# RF-UNIT.net
KiCad netlist of a schematic drawn in Altium Designer
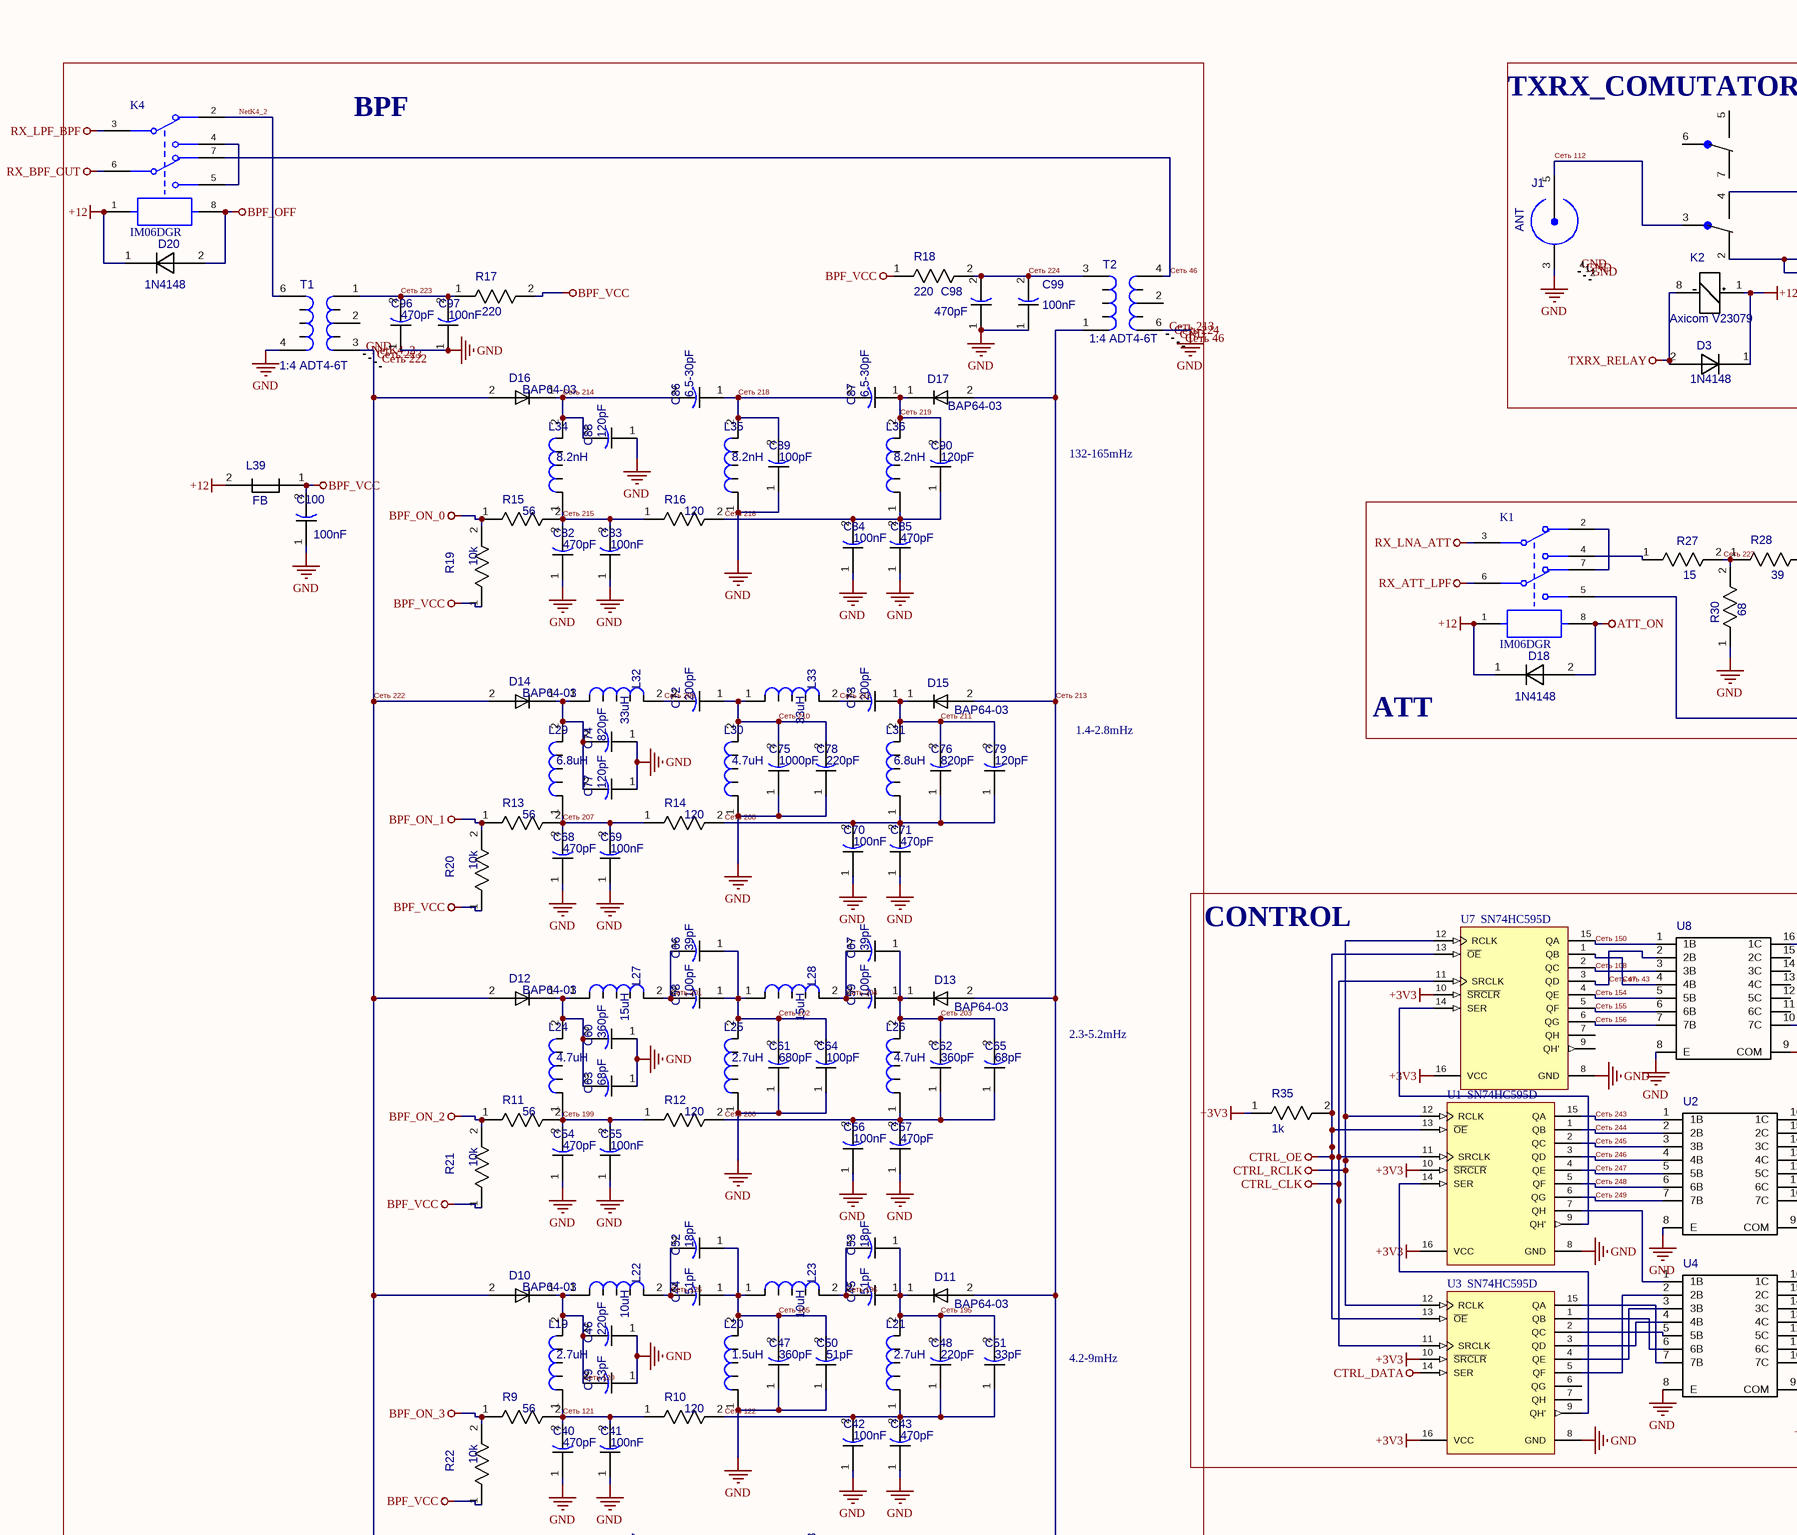
[diagram p0: RF-UNIT.SCHDOC, top left]
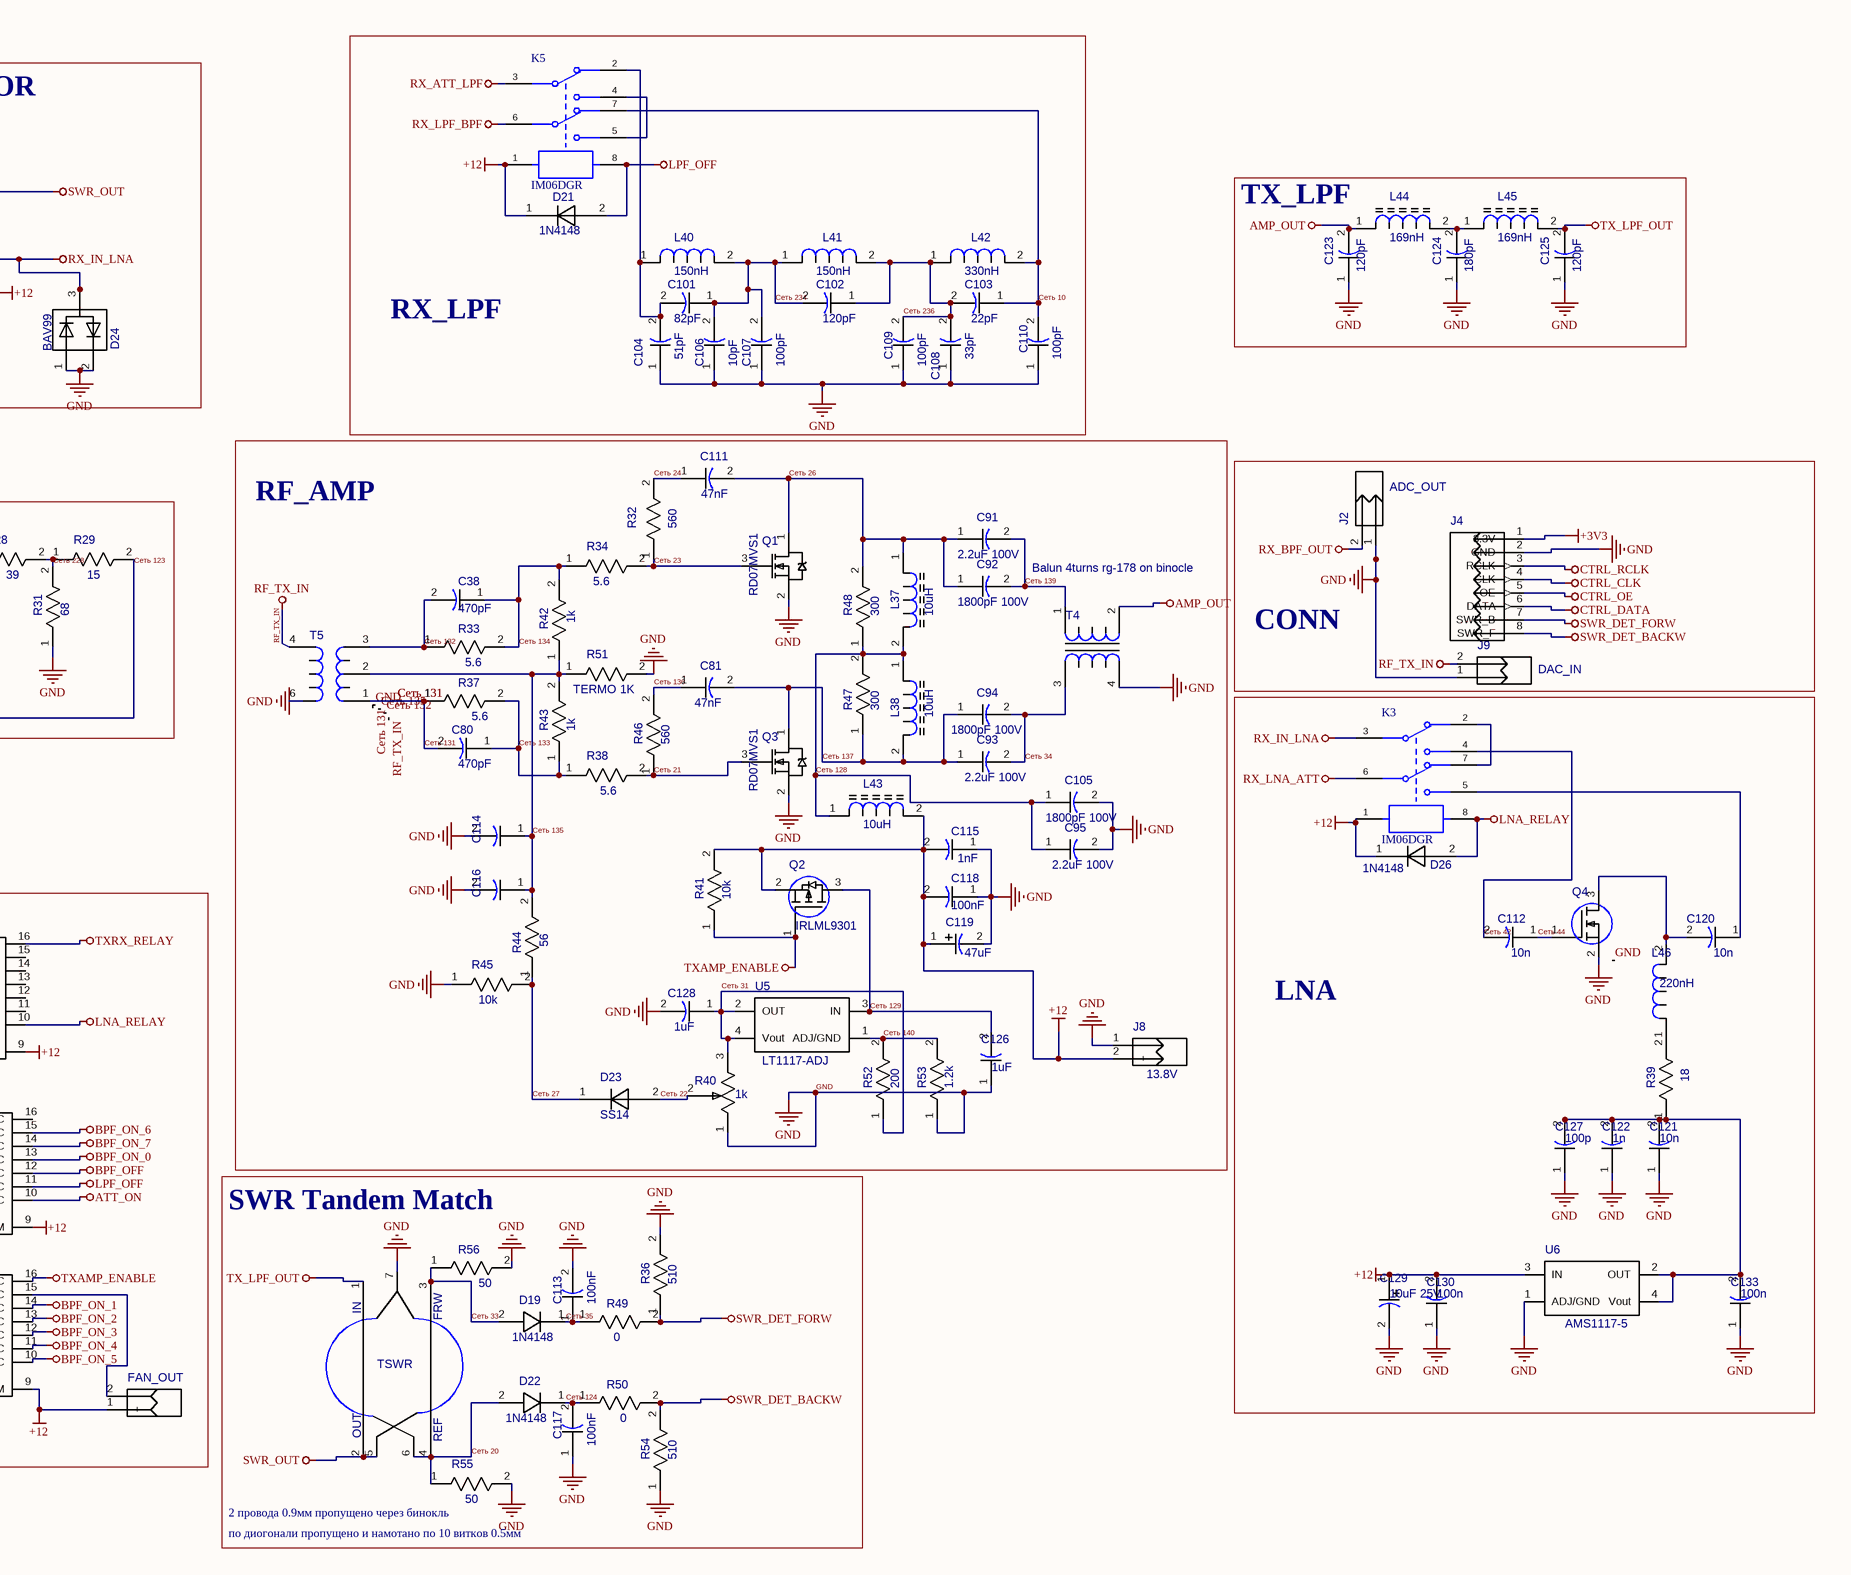
[diagram p1: RF-UNIT.SCHDOC, top right]
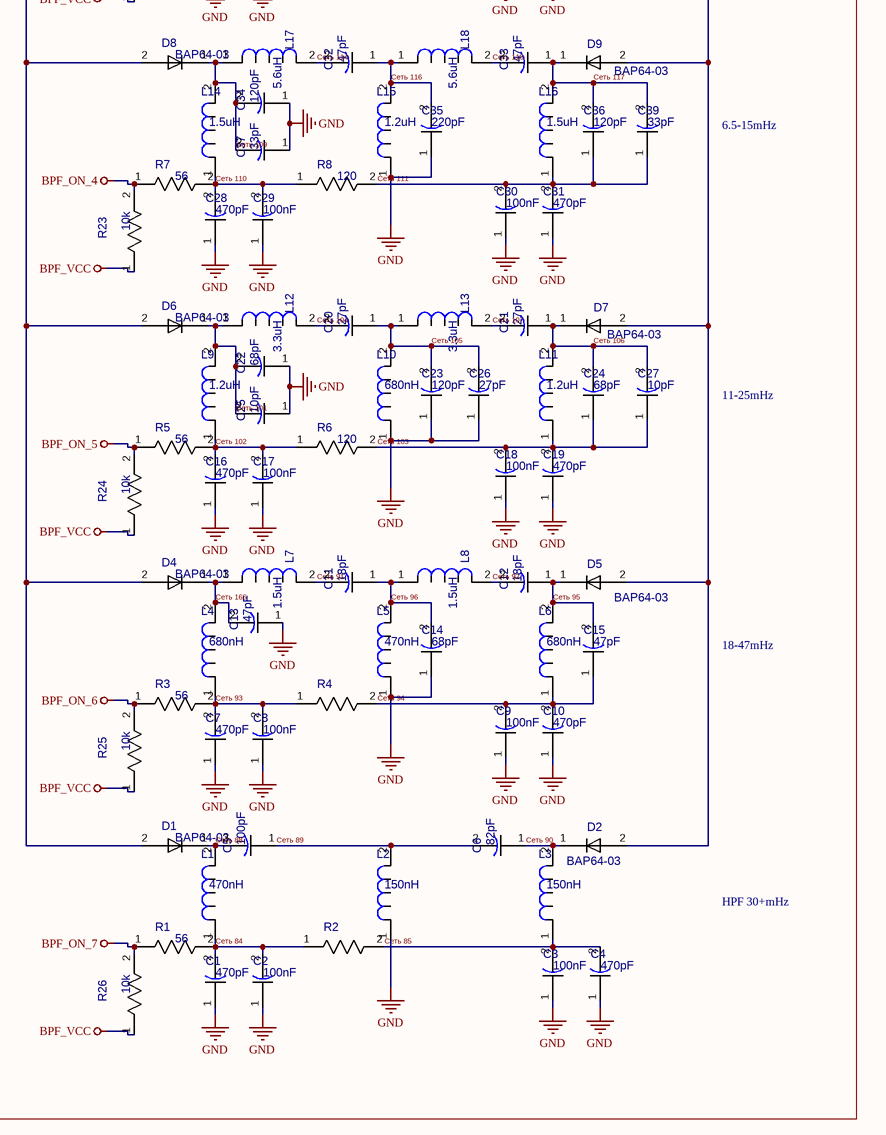
[diagram p2: RF-UNIT.SCHDOC, bottom left]

(export (version "E")
  (design (tool "Eeschema 10.0.6"))
  (components
    (comp (ref "C1")
      (value "470pF")
      (footprint "CAP_0805")
      (description "CAP_0805")
      (libsource (lib "*") (part "CAP_0805"))
    )
    (comp (ref "C2")
      (value "100nF")
      (footprint "CAP_0805")
      (description "CAP_0805")
      (libsource (lib "*") (part "CAP_0805"))
    )
    (comp (ref "C3")
      (value "100nF")
      (footprint "CAP_0805")
      (description "CAP_0805")
      (libsource (lib "*") (part "CAP_0805"))
    )
    (comp (ref "C4")
      (value "470pF")
      (footprint "CAP_0805")
      (description "CAP_0805")
      (libsource (lib "*") (part "CAP_0805"))
    )
    (comp (ref "C5")
      (value "100pF")
      (footprint "CAP_0805")
      (description "CAP_0805")
      (libsource (lib "*") (part "CAP_0805"))
    )
    (comp (ref "C6")
      (value "82pF")
      (footprint "CAP_0805")
      (description "CAP_0805")
      (libsource (lib "*") (part "CAP_0805"))
    )
    (comp (ref "C7")
      (value "470pF")
      (footprint "CAP_0805")
      (description "CAP_0805")
      (libsource (lib "*") (part "CAP_0805"))
    )
    (comp (ref "C8")
      (value "100nF")
      (footprint "CAP_0805")
      (description "CAP_0805")
      (libsource (lib "*") (part "CAP_0805"))
    )
    (comp (ref "C9")
      (value "100nF")
      (footprint "CAP_0805")
      (description "CAP_0805")
      (libsource (lib "*") (part "CAP_0805"))
    )
    (comp (ref "C10")
      (value "470pF")
      (footprint "CAP_0805")
      (description "CAP_0805")
      (libsource (lib "*") (part "CAP_0805"))
    )
    (comp (ref "C11")
      (value "18pF")
      (footprint "CAP_0805")
      (description "CAP_0805")
      (libsource (lib "*") (part "CAP_0805"))
    )
    (comp (ref "C12")
      (value "18pF")
      (footprint "CAP_0805")
      (description "CAP_0805")
      (libsource (lib "*") (part "CAP_0805"))
    )
    (comp (ref "C13")
      (value "47pF")
      (footprint "CAP_0805")
      (description "CAP_0805")
      (libsource (lib "*") (part "CAP_0805"))
    )
    (comp (ref "C14")
      (value "68pF")
      (footprint "CAP_0805")
      (description "CAP_0805")
      (libsource (lib "*") (part "CAP_0805"))
    )
    (comp (ref "C15")
      (value "47pF")
      (footprint "CAP_0805")
      (description "CAP_0805")
      (libsource (lib "*") (part "CAP_0805"))
    )
    (comp (ref "C16")
      (value "470pF")
      (footprint "CAP_0805")
      (description "CAP_0805")
      (libsource (lib "*") (part "CAP_0805"))
    )
    (comp (ref "C17")
      (value "100nF")
      (footprint "CAP_0805")
      (description "CAP_0805")
      (libsource (lib "*") (part "CAP_0805"))
    )
    (comp (ref "C18")
      (value "100nF")
      (footprint "CAP_0805")
      (description "CAP_0805")
      (libsource (lib "*") (part "CAP_0805"))
    )
    (comp (ref "C19")
      (value "470pF")
      (footprint "CAP_0805")
      (description "CAP_0805")
      (libsource (lib "*") (part "CAP_0805"))
    )
    (comp (ref "C20")
      (value "27pF")
      (footprint "CAP_0805")
      (description "CAP_0805")
      (libsource (lib "*") (part "CAP_0805"))
    )
    (comp (ref "C21")
      (value "27pF")
      (footprint "CAP_0805")
      (description "CAP_0805")
      (libsource (lib "*") (part "CAP_0805"))
    )
    (comp (ref "C22")
      (value "68pF")
      (footprint "CAP_0805")
      (description "CAP_0805")
      (libsource (lib "*") (part "CAP_0805"))
    )
    (comp (ref "C23")
      (value "120pF")
      (footprint "CAP_0805")
      (description "CAP_0805")
      (libsource (lib "*") (part "CAP_0805"))
    )
    (comp (ref "C24")
      (value "68pF")
      (footprint "CAP_0805")
      (description "CAP_0805")
      (libsource (lib "*") (part "CAP_0805"))
    )
    (comp (ref "C25")
      (value "10pF")
      (footprint "CAP_0805")
      (description "CAP_0805")
      (libsource (lib "*") (part "CAP_0805"))
    )
    (comp (ref "C26")
      (value "27pF")
      (footprint "CAP_0805")
      (description "CAP_0805")
      (libsource (lib "*") (part "CAP_0805"))
    )
    (comp (ref "C27")
      (value "10pF")
      (footprint "CAP_0805")
      (description "CAP_0805")
      (libsource (lib "*") (part "CAP_0805"))
    )
    (comp (ref "C28")
      (value "470pF")
      (footprint "CAP_0805")
      (description "CAP_0805")
      (libsource (lib "*") (part "CAP_0805"))
    )
    (comp (ref "C29")
      (value "100nF")
      (footprint "CAP_0805")
      (description "CAP_0805")
      (libsource (lib "*") (part "CAP_0805"))
    )
    (comp (ref "C30")
      (value "100nF")
      (footprint "CAP_0805")
      (description "CAP_0805")
      (libsource (lib "*") (part "CAP_0805"))
    )
    (comp (ref "C31")
      (value "470pF")
      (footprint "CAP_0805")
      (description "CAP_0805")
      (libsource (lib "*") (part "CAP_0805"))
    )
    (comp (ref "C32")
      (value "47pF")
      (footprint "CAP_0805")
      (description "CAP_0805")
      (libsource (lib "*") (part "CAP_0805"))
    )
    (comp (ref "C33")
      (value "47pF")
      (footprint "CAP_0805")
      (description "CAP_0805")
      (libsource (lib "*") (part "CAP_0805"))
    )
    (comp (ref "C34")
      (value "120pF")
      (footprint "CAP_0805")
      (description "CAP_0805")
      (libsource (lib "*") (part "CAP_0805"))
    )
    (comp (ref "C35")
      (value "220pF")
      (footprint "CAP_0805")
      (description "CAP_0805")
      (libsource (lib "*") (part "CAP_0805"))
    )
    (comp (ref "C36")
      (value "120pF")
      (footprint "CAP_0805")
      (description "CAP_0805")
      (libsource (lib "*") (part "CAP_0805"))
    )
    (comp (ref "C37")
      (value "33pF")
      (footprint "CAP_0805")
      (description "CAP_0805")
      (libsource (lib "*") (part "CAP_0805"))
    )
    (comp (ref "C38")
      (value "470pF")
      (footprint "CAP_0805")
      (description "CAP_0805")
      (libsource (lib "*") (part "CAP_0805"))
    )
    (comp (ref "C39")
      (value "33pF")
      (footprint "CAP_0805")
      (description "CAP_0805")
      (libsource (lib "*") (part "CAP_0805"))
    )
    (comp (ref "C40")
      (value "470pF")
      (footprint "CAP_0805")
      (description "CAP_0805")
      (libsource (lib "*") (part "CAP_0805"))
    )
    (comp (ref "C41")
      (value "100nF")
      (footprint "CAP_0805")
      (description "CAP_0805")
      (libsource (lib "*") (part "CAP_0805"))
    )
    (comp (ref "C42")
      (value "100nF")
      (footprint "CAP_0805")
      (description "CAP_0805")
      (libsource (lib "*") (part "CAP_0805"))
    )
    (comp (ref "C43")
      (value "470pF")
      (footprint "CAP_0805")
      (description "CAP_0805")
      (libsource (lib "*") (part "CAP_0805"))
    )
    (comp (ref "C44")
      (value "51pF")
      (footprint "CAP_0805")
      (description "CAP_0805")
      (libsource (lib "*") (part "CAP_0805"))
    )
    (comp (ref "C45")
      (value "51pF")
      (footprint "CAP_0805")
      (description "CAP_0805")
      (libsource (lib "*") (part "CAP_0805"))
    )
    (comp (ref "C46")
      (value "220pF")
      (footprint "CAP_0805")
      (description "CAP_0805")
      (libsource (lib "*") (part "CAP_0805"))
    )
    (comp (ref "C47")
      (value "360pF")
      (footprint "CAP_0805")
      (description "CAP_0805")
      (libsource (lib "*") (part "CAP_0805"))
    )
    (comp (ref "C48")
      (value "220pF")
      (footprint "CAP_0805")
      (description "CAP_0805")
      (libsource (lib "*") (part "CAP_0805"))
    )
    (comp (ref "C49")
      (value "33pF")
      (footprint "CAP_0805")
      (description "CAP_0805")
      (libsource (lib "*") (part "CAP_0805"))
    )
    (comp (ref "C50")
      (value "51pF")
      (footprint "CAP_0805")
      (description "CAP_0805")
      (libsource (lib "*") (part "CAP_0805"))
    )
    (comp (ref "C51")
      (value "33pF")
      (footprint "CAP_0805")
      (description "CAP_0805")
      (libsource (lib "*") (part "CAP_0805"))
    )
    (comp (ref "C52")
      (value "18pF")
      (footprint "CAP_0805")
      (description "CAP_0805")
      (libsource (lib "*") (part "CAP_0805"))
    )
    (comp (ref "C53")
      (value "18pF")
      (footprint "CAP_0805")
      (description "CAP_0805")
      (libsource (lib "*") (part "CAP_0805"))
    )
    (comp (ref "C54")
      (value "470pF")
      (footprint "CAP_0805")
      (description "CAP_0805")
      (libsource (lib "*") (part "CAP_0805"))
    )
    (comp (ref "C55")
      (value "100nF")
      (footprint "CAP_0805")
      (description "CAP_0805")
      (libsource (lib "*") (part "CAP_0805"))
    )
    (comp (ref "C56")
      (value "100nF")
      (footprint "CAP_0805")
      (description "CAP_0805")
      (libsource (lib "*") (part "CAP_0805"))
    )
    (comp (ref "C57")
      (value "470pF")
      (footprint "CAP_0805")
      (description "CAP_0805")
      (libsource (lib "*") (part "CAP_0805"))
    )
    (comp (ref "C58")
      (value "100pF")
      (footprint "CAP_0805")
      (description "CAP_0805")
      (libsource (lib "*") (part "CAP_0805"))
    )
    (comp (ref "C59")
      (value "100pF")
      (footprint "CAP_0805")
      (description "CAP_0805")
      (libsource (lib "*") (part "CAP_0805"))
    )
    (comp (ref "C60")
      (value "360pF")
      (footprint "CAP_0805")
      (description "CAP_0805")
      (libsource (lib "*") (part "CAP_0805"))
    )
    (comp (ref "C61")
      (value "680pF")
      (footprint "CAP_0805")
      (description "CAP_0805")
      (libsource (lib "*") (part "CAP_0805"))
    )
    (comp (ref "C62")
      (value "360pF")
      (footprint "CAP_0805")
      (description "CAP_0805")
      (libsource (lib "*") (part "CAP_0805"))
    )
    (comp (ref "C63")
      (value "68pF")
      (footprint "CAP_0805")
      (description "CAP_0805")
      (libsource (lib "*") (part "CAP_0805"))
    )
    (comp (ref "C64")
      (value "100pF")
      (footprint "CAP_0805")
      (description "CAP_0805")
      (libsource (lib "*") (part "CAP_0805"))
    )
    (comp (ref "C65")
      (value "68pF")
      (footprint "CAP_0805")
      (description "CAP_0805")
      (libsource (lib "*") (part "CAP_0805"))
    )
    (comp (ref "C66")
      (value "39pF")
      (footprint "CAP_0805")
      (description "CAP_0805")
      (libsource (lib "*") (part "CAP_0805"))
    )
    (comp (ref "C67")
      (value "39pF")
      (footprint "CAP_0805")
      (description "CAP_0805")
      (libsource (lib "*") (part "CAP_0805"))
    )
    (comp (ref "C68")
      (value "470pF")
      (footprint "CAP_0805")
      (description "CAP_0805")
      (libsource (lib "*") (part "CAP_0805"))
    )
    (comp (ref "C69")
      (value "100nF")
      (footprint "CAP_0805")
      (description "CAP_0805")
      (libsource (lib "*") (part "CAP_0805"))
    )
    (comp (ref "C70")
      (value "100nF")
      (footprint "CAP_0805")
      (description "CAP_0805")
      (libsource (lib "*") (part "CAP_0805"))
    )
    (comp (ref "C71")
      (value "470pF")
      (footprint "CAP_0805")
      (description "CAP_0805")
      (libsource (lib "*") (part "CAP_0805"))
    )
    (comp (ref "C72")
      (value "200pF")
      (footprint "CAP_0805")
      (description "CAP_0805")
      (libsource (lib "*") (part "CAP_0805"))
    )
    (comp (ref "C73")
      (value "200pF")
      (footprint "CAP_0805")
      (description "CAP_0805")
      (libsource (lib "*") (part "CAP_0805"))
    )
    (comp (ref "C74")
      (value "820pF")
      (footprint "CAP_0805")
      (description "CAP_0805")
      (libsource (lib "*") (part "CAP_0805"))
    )
    (comp (ref "C75")
      (value "1000pF")
      (footprint "CAP_0805")
      (description "CAP_0805")
      (libsource (lib "*") (part "CAP_0805"))
    )
    (comp (ref "C76")
      (value "820pF")
      (footprint "CAP_0805")
      (description "CAP_0805")
      (libsource (lib "*") (part "CAP_0805"))
    )
    (comp (ref "C77")
      (value "120pF")
      (footprint "CAP_0805")
      (description "CAP_0805")
      (libsource (lib "*") (part "CAP_0805"))
    )
    (comp (ref "C78")
      (value "220pF")
      (footprint "CAP_0805")
      (description "CAP_0805")
      (libsource (lib "*") (part "CAP_0805"))
    )
    (comp (ref "C79")
      (value "120pF")
      (footprint "CAP_0805")
      (description "CAP_0805")
      (libsource (lib "*") (part "CAP_0805"))
    )
    (comp (ref "C80")
      (value "470pF")
      (footprint "CAP_0805")
      (description "CAP_0805")
      (libsource (lib "*") (part "CAP_0805"))
    )
    (comp (ref "C81")
      (value "47nF")
      (footprint "CAP_1206")
      (description "CAP_1206")
      (libsource (lib "*") (part "CAP_1206"))
    )
    (comp (ref "C82")
      (value "470pF")
      (footprint "CAP_0805")
      (description "CAP_0805")
      (libsource (lib "*") (part "CAP_0805"))
    )
    (comp (ref "C83")
      (value "100nF")
      (footprint "CAP_0805")
      (description "CAP_0805")
      (libsource (lib "*") (part "CAP_0805"))
    )
    (comp (ref "C84")
      (value "100nF")
      (footprint "CAP_0805")
      (description "CAP_0805")
      (libsource (lib "*") (part "CAP_0805"))
    )
    (comp (ref "C85")
      (value "470pF")
      (footprint "CAP_0805")
      (description "CAP_0805")
      (libsource (lib "*") (part "CAP_0805"))
    )
    (comp (ref "C86")
      (value "6.5-30pF")
      (footprint "CAP_1206")
      (description "CAP_0805")
      (libsource (lib "*") (part "CAP_0805"))
    )
    (comp (ref "C87")
      (value "6.5-30pF")
      (footprint "CAP_1206")
      (description "CAP_0805")
      (libsource (lib "*") (part "CAP_0805"))
    )
    (comp (ref "C88")
      (value "120pF")
      (footprint "CAP_0805")
      (description "CAP_0805")
      (libsource (lib "*") (part "CAP_0805"))
    )
    (comp (ref "C89")
      (value "100pF")
      (footprint "CAP_0805")
      (description "CAP_0805")
      (libsource (lib "*") (part "CAP_0805"))
    )
    (comp (ref "C90")
      (value "120pF")
      (footprint "CAP_0805")
      (description "CAP_0805")
      (libsource (lib "*") (part "CAP_0805"))
    )
    (comp (ref "C91")
      (value "2.2uF 100V")
      (footprint "CAP_1206")
      (description "CAP_1206")
      (libsource (lib "*") (part "CAP_1206"))
    )
    (comp (ref "C92")
      (value "1800pF 100V")
      (footprint "CAP_1206")
      (description "CAP_1206")
      (libsource (lib "*") (part "CAP_1206"))
    )
    (comp (ref "C93")
      (value "2.2uF 100V")
      (footprint "CAP_1206")
      (description "CAP_1206")
      (libsource (lib "*") (part "CAP_1206"))
    )
    (comp (ref "C94")
      (value "1800pF 100V")
      (footprint "CAP_1206")
      (description "CAP_1206")
      (libsource (lib "*") (part "CAP_1206"))
    )
    (comp (ref "C95")
      (value "2.2uF 100V")
      (footprint "CAP_1206")
      (description "CAP_1206")
      (libsource (lib "*") (part "CAP_1206"))
    )
    (comp (ref "C96")
      (value "470pF")
      (footprint "CAP_0805")
      (description "CAP_0805")
      (libsource (lib "*") (part "CAP_0805"))
    )
    (comp (ref "C97")
      (value "100nF")
      (footprint "CAP_0805")
      (description "CAP_0805")
      (libsource (lib "*") (part "CAP_0805"))
    )
    (comp (ref "C98")
      (value "470pF")
      (footprint "CAP_0805")
      (description "CAP_0805")
      (libsource (lib "*") (part "CAP_0805"))
    )
    (comp (ref "C99")
      (value "100nF")
      (footprint "CAP_0805")
      (description "CAP_0805")
      (libsource (lib "*") (part "CAP_0805"))
    )
    (comp (ref "C100")
      (value "100nF")
      (footprint "CAP_0805")
      (description "CAP_0805")
      (libsource (lib "*") (part "CAP_0805"))
    )
    (comp (ref "C101")
      (value "82pF")
      (footprint "CAP_0805")
      (description "CAP_0805")
      (libsource (lib "*") (part "CAP_0805"))
    )
    (comp (ref "C102")
      (value "120pF")
      (footprint "CAP_0805")
      (description "CAP_0805")
      (libsource (lib "*") (part "CAP_0805"))
    )
    (comp (ref "C103")
      (value "22pF")
      (footprint "CAP_0805")
      (description "CAP_0805")
      (libsource (lib "*") (part "CAP_0805"))
    )
    (comp (ref "C104")
      (value "51pF")
      (footprint "CAP_0805")
      (description "CAP_0805")
      (libsource (lib "*") (part "CAP_0805"))
    )
    (comp (ref "C105")
      (value "1800pF 100V")
      (footprint "CAP_1206")
      (description "CAP_1206")
      (libsource (lib "*") (part "CAP_1206"))
    )
    (comp (ref "C106")
      (value "10pF")
      (footprint "CAP_0805")
      (description "CAP_0805")
      (libsource (lib "*") (part "CAP_0805"))
    )
    (comp (ref "C107")
      (value "100pF")
      (footprint "CAP_0805")
      (description "CAP_0805")
      (libsource (lib "*") (part "CAP_0805"))
    )
    (comp (ref "C108")
      (value "33pF")
      (footprint "CAP_0805")
      (description "CAP_0805")
      (libsource (lib "*") (part "CAP_0805"))
    )
    (comp (ref "C109")
      (value "100pF")
      (footprint "CAP_0805")
      (description "CAP_0805")
      (libsource (lib "*") (part "CAP_0805"))
    )
    (comp (ref "C110")
      (value "100pF")
      (footprint "CAP_0805")
      (description "CAP_0805")
      (libsource (lib "*") (part "CAP_0805"))
    )
    (comp (ref "C111")
      (value "47nF")
      (footprint "CAP_1206")
      (description "CAP_1206")
      (libsource (lib "*") (part "CAP_1206"))
    )
    (comp (ref "C112")
      (value "10n")
      (footprint "CAP_0805")
      (description "CAP_0805")
      (libsource (lib "*") (part "CAP_0805"))
    )
    (comp (ref "C113")
      (value "100nF")
      (footprint "CAP_0805")
      (description "CAP_0805")
      (libsource (lib "*") (part "CAP_0805"))
    )
    (comp (ref "C114") (value "CAP_0805") (footprint "CAP_0805") (libsource (lib "*") (part "CAP_0805")))
    (comp (ref "C115")
      (value "1nF")
      (footprint "CAP_0805")
      (description "CAP_0805")
      (libsource (lib "*") (part "CAP_0805"))
    )
    (comp (ref "C116") (value "CAP_0805") (footprint "CAP_0805") (libsource (lib "*") (part "CAP_0805")))
    (comp (ref "C117")
      (value "100nF")
      (footprint "CAP_0805")
      (description "CAP_0805")
      (libsource (lib "*") (part "CAP_0805"))
    )
    (comp (ref "C118")
      (value "100nF")
      (footprint "CAP_0805")
      (description "CAP_0805")
      (libsource (lib "*") (part "CAP_0805"))
    )
    (comp (ref "C119")
      (value "47uF")
      (footprint "CAPAE_6.6x6.6h5.4")
      (description "CAPAE_6.6x6.6h5.4")
      (libsource (lib "*") (part "CAPAE_6.6x6.6h5.4"))
    )
    (comp (ref "C120")
      (value "10n")
      (footprint "CAP_0805")
      (description "CAP_0805")
      (libsource (lib "*") (part "CAP_0805"))
    )
    (comp (ref "C121")
      (value "10n")
      (footprint "6-0805_M")
      (description "CAP_0805")
      (libsource (lib "*") (part "CAP_0805"))
    )
    (comp (ref "C122")
      (value "1n")
      (footprint "6-0805_M")
      (description "CAP_0805")
      (libsource (lib "*") (part "CAP_0805"))
    )
    (comp (ref "C123")
      (value "120pF")
      (footprint "CAP_1206")
      (description "CAP_1206")
      (libsource (lib "*") (part "CAP_1206"))
    )
    (comp (ref "C124")
      (value "180pF")
      (footprint "CAP_1206")
      (description "CAP_1206")
      (libsource (lib "*") (part "CAP_1206"))
    )
    (comp (ref "C125")
      (value "120pF")
      (footprint "CAP_1206")
      (description "CAP_1206")
      (libsource (lib "*") (part "CAP_1206"))
    )
    (comp (ref "C126")
      (value "1uF")
      (footprint "CAP_0805")
      (description "CAP_0805")
      (libsource (lib "*") (part "CAP_0805"))
    )
    (comp (ref "C127")
      (value "100p")
      (footprint "6-0805_M")
      (description "CAP_0805")
      (libsource (lib "*") (part "CAP_0805"))
    )
    (comp (ref "C128")
      (value "1uF")
      (footprint "CAP_0805")
      (description "CAP_0805")
      (libsource (lib "*") (part "CAP_0805"))
    )
    (comp (ref "C129")
      (value "10uF 25V")
      (footprint "CAPAE_5.3x5.3h6.1")
      (description "CAPAE_5.3x5.3h6.1")
      (libsource (lib "*") (part "CAPAE_5.3x5.3h6.1"))
    )
    (comp (ref "C130")
      (value "100n")
      (footprint "CAP_0805")
      (description "CAP_0805")
      (libsource (lib "*") (part "CAP_0805"))
    )
    (comp (ref "C133")
      (value "100n")
      (footprint "CAP_0805")
      (description "CAP_0805")
      (libsource (lib "*") (part "CAP_0805"))
    )
    (comp (ref "D1") (value "BAP64-03") (footprint "SOD-323") (libsource (lib "*") (part "BAP64-03")))
    (comp (ref "D2") (value "BAP64-03") (footprint "SOD-323") (libsource (lib "*") (part "BAP64-03")))
    (comp (ref "D3") (value "1N4148") (footprint "1N4148") (libsource (lib "*") (part "1N4148")))
    (comp (ref "D4") (value "BAP64-03") (footprint "SOD-323") (libsource (lib "*") (part "BAP64-03")))
    (comp (ref "D5") (value "BAP64-03") (footprint "SOD-323") (libsource (lib "*") (part "BAP64-03")))
    (comp (ref "D6") (value "BAP64-03") (footprint "SOD-323") (libsource (lib "*") (part "BAP64-03")))
    (comp (ref "D7") (value "BAP64-03") (footprint "SOD-323") (libsource (lib "*") (part "BAP64-03")))
    (comp (ref "D8") (value "BAP64-03") (footprint "SOD-323") (libsource (lib "*") (part "BAP64-03")))
    (comp (ref "D9") (value "BAP64-03") (footprint "SOD-323") (libsource (lib "*") (part "BAP64-03")))
    (comp (ref "D10") (value "BAP64-03") (footprint "SOD-323") (libsource (lib "*") (part "BAP64-03")))
    (comp (ref "D11") (value "BAP64-03") (footprint "SOD-323") (libsource (lib "*") (part "BAP64-03")))
    (comp (ref "D12") (value "BAP64-03") (footprint "SOD-323") (libsource (lib "*") (part "BAP64-03")))
    (comp (ref "D13") (value "BAP64-03") (footprint "SOD-323") (libsource (lib "*") (part "BAP64-03")))
    (comp (ref "D14") (value "BAP64-03") (footprint "SOD-323") (libsource (lib "*") (part "BAP64-03")))
    (comp (ref "D15") (value "BAP64-03") (footprint "SOD-323") (libsource (lib "*") (part "BAP64-03")))
    (comp (ref "D16") (value "BAP64-03") (footprint "SOD-323") (libsource (lib "*") (part "BAP64-03")))
    (comp (ref "D17") (value "BAP64-03") (footprint "SOD-323") (libsource (lib "*") (part "BAP64-03")))
    (comp (ref "D18") (value "1N4148") (footprint "1N4148") (libsource (lib "*") (part "1N4148")))
    (comp (ref "D19")
      (value "1N4148")
      (footprint "DIODE_1206")
      (description "DIODE_1206")
      (libsource (lib "*") (part "DIODE_1206"))
    )
    (comp (ref "D20") (value "1N4148") (footprint "1N4148") (libsource (lib "*") (part "1N4148")))
    (comp (ref "D21") (value "1N4148") (footprint "1N4148") (libsource (lib "*") (part "1N4148")))
    (comp (ref "D22")
      (value "1N4148")
      (footprint "DIODE_1206")
      (description "DIODE_1206")
      (libsource (lib "*") (part "DIODE_1206"))
    )
    (comp (ref "D23") (value "SS14") (footprint "SS14") (libsource (lib "*") (part "SS14")))
    (comp (ref "D24") (value "BAV99") (footprint "SOT23") (libsource (lib "*") (part "BAV99")))
    (comp (ref "D26") (value "1N4148") (footprint "1N4148") (libsource (lib "*") (part "1N4148")))
    (comp (ref "FAN_OUT")
      (value "51022-0200")
      (footprint "51022-0200")
      (libsource (lib "*") (part "51022-0200"))
    )
    (comp (ref "J1")
      (value "ANT")
      (footprint "31-5431")
      (description "31-5431")
      (libsource (lib "*") (part "31-5431"))
    )
    (comp (ref "J2")
      (value "ADC_OUT")
      (footprint "644456-2")
      (description "644456-2")
      (libsource (lib "*") (part "644456-2"))
    )
    (comp (ref "J4") (value "90131-0124") (footprint "90131-0124") (libsource (lib "*") (part "90131-0124")))
    (comp (ref "J8")
      (value "13.8V")
      (footprint "1986717-2")
      (description "1986717-2")
      (libsource (lib "*") (part "1986717-2"))
    )
    (comp (ref "J9")
      (value "DAC_IN")
      (footprint "644456-2")
      (description "644456-2")
      (libsource (lib "*") (part "644456-2"))
    )
    (comp (ref "K1")
      (value "IM06DGR")
      (footprint "TECO-SMT-8_V")
      (description "Signal Relay, 5 A, 12 VDC, -40 to 85 degC, 8-Pin SMD, RoHS, Tape and Reel")
      (fields
        (field (name "MANUFACTURER") "TE Connectivity")
        (field (name "APPROVAL CATEGORY") "ULRecognised")
        (field (name "APPROVAL BODIES") "EN/IEC")
      )
      (libsource (lib "Altium Content Vault") (part "RELAY-DPDT-8_C"))
    )
    (comp (ref "K2")
      (value "Axicom V23079")
      (footprint "V23079")
      (libsource (lib "RF-UNIT") (part "Axicom V23079"))
    )
    (comp (ref "K3")
      (value "IM06DGR")
      (footprint "TECO-SMT-8_V")
      (description "Signal Relay, 5 A, 12 VDC, -40 to 85 degC, 8-Pin SMD, RoHS, Tape and Reel")
      (fields
        (field (name "MANUFACTURER") "TE Connectivity")
        (field (name "APPROVAL CATEGORY") "ULRecognised")
        (field (name "APPROVAL BODIES") "EN/IEC")
      )
      (libsource (lib "Altium Content Vault") (part "RELAY-DPDT-8_C"))
    )
    (comp (ref "K4")
      (value "IM06DGR")
      (footprint "TECO-SMT-8_V")
      (description "Signal Relay, 5 A, 12 VDC, -40 to 85 degC, 8-Pin SMD, RoHS, Tape and Reel")
      (fields
        (field (name "MANUFACTURER") "TE Connectivity")
        (field (name "APPROVAL CATEGORY") "ULRecognised")
        (field (name "APPROVAL BODIES") "EN/IEC")
      )
      (libsource (lib "Altium Content Vault") (part "RELAY-DPDT-8_C"))
    )
    (comp (ref "K5")
      (value "IM06DGR")
      (footprint "TECO-SMT-8_V")
      (description "Signal Relay, 5 A, 12 VDC, -40 to 85 degC, 8-Pin SMD, RoHS, Tape and Reel")
      (fields
        (field (name "MANUFACTURER") "TE Connectivity")
        (field (name "APPROVAL CATEGORY") "ULRecognised")
        (field (name "APPROVAL BODIES") "EN/IEC")
      )
      (libsource (lib "Altium Content Vault") (part "RELAY-DPDT-8_C"))
    )
    (comp (ref "L1")
      (value "470nH")
      (footprint "IND_0805")
      (description "IND_0805")
      (libsource (lib "*") (part "IND_0805"))
    )
    (comp (ref "L2")
      (value "150nH")
      (footprint "IND_0805")
      (description "IND_0805")
      (libsource (lib "*") (part "IND_0805"))
    )
    (comp (ref "L3")
      (value "150nH")
      (footprint "IND_0805")
      (description "IND_0805")
      (libsource (lib "*") (part "IND_0805"))
    )
    (comp (ref "L4")
      (value "680nH")
      (footprint "IND_0805")
      (description "IND_0805")
      (libsource (lib "*") (part "IND_0805"))
    )
    (comp (ref "L5")
      (value "470nH")
      (footprint "IND_0805")
      (description "IND_0805")
      (libsource (lib "*") (part "IND_0805"))
    )
    (comp (ref "L6")
      (value "680nH")
      (footprint "IND_0805")
      (description "IND_0805")
      (libsource (lib "*") (part "IND_0805"))
    )
    (comp (ref "L7")
      (value "1.5uH")
      (footprint "IND_0805")
      (description "IND_0805")
      (libsource (lib "*") (part "IND_0805"))
    )
    (comp (ref "L8")
      (value "1.5uH")
      (footprint "IND_0805")
      (description "IND_0805")
      (libsource (lib "*") (part "IND_0805"))
    )
    (comp (ref "L9")
      (value "1.2uH")
      (footprint "IND_0805")
      (description "IND_0805")
      (libsource (lib "*") (part "IND_0805"))
    )
    (comp (ref "L10")
      (value "680nH")
      (footprint "IND_0805")
      (description "IND_0805")
      (libsource (lib "*") (part "IND_0805"))
    )
    (comp (ref "L11")
      (value "1.2uH")
      (footprint "IND_0805")
      (description "IND_0805")
      (libsource (lib "*") (part "IND_0805"))
    )
    (comp (ref "L12")
      (value "3.3uH")
      (footprint "IND_0805")
      (description "IND_0805")
      (libsource (lib "*") (part "IND_0805"))
    )
    (comp (ref "L13")
      (value "3.3uH")
      (footprint "IND_0805")
      (description "IND_0805")
      (libsource (lib "*") (part "IND_0805"))
    )
    (comp (ref "L14")
      (value "1.5uH")
      (footprint "IND_0805")
      (description "IND_0805")
      (libsource (lib "*") (part "IND_0805"))
    )
    (comp (ref "L15")
      (value "1.2uH")
      (footprint "IND_0805")
      (description "IND_0805")
      (libsource (lib "*") (part "IND_0805"))
    )
    (comp (ref "L16")
      (value "1.5uH")
      (footprint "IND_0805")
      (description "IND_0805")
      (libsource (lib "*") (part "IND_0805"))
    )
    (comp (ref "L17")
      (value "5.6uH")
      (footprint "IND_0805")
      (description "IND_0805")
      (libsource (lib "*") (part "IND_0805"))
    )
    (comp (ref "L18")
      (value "5.6uH")
      (footprint "IND_0805")
      (description "IND_0805")
      (libsource (lib "*") (part "IND_0805"))
    )
    (comp (ref "L19")
      (value "2.7uH")
      (footprint "IND_0805")
      (description "IND_0805")
      (libsource (lib "*") (part "IND_0805"))
    )
    (comp (ref "L20")
      (value "1.5uH")
      (footprint "IND_0805")
      (description "IND_0805")
      (libsource (lib "*") (part "IND_0805"))
    )
    (comp (ref "L21")
      (value "2.7uH")
      (footprint "IND_0805")
      (description "IND_0805")
      (libsource (lib "*") (part "IND_0805"))
    )
    (comp (ref "L22")
      (value "10uH")
      (footprint "IND_0805")
      (description "IND_0805")
      (libsource (lib "*") (part "IND_0805"))
    )
    (comp (ref "L23")
      (value "10uH")
      (footprint "IND_0805")
      (description "IND_0805")
      (libsource (lib "*") (part "IND_0805"))
    )
    (comp (ref "L24")
      (value "4.7uH")
      (footprint "IND_0805")
      (description "IND_0805")
      (libsource (lib "*") (part "IND_0805"))
    )
    (comp (ref "L25")
      (value "2.7uH")
      (footprint "IND_0805")
      (description "IND_0805")
      (libsource (lib "*") (part "IND_0805"))
    )
    (comp (ref "L26")
      (value "4.7uH")
      (footprint "IND_0805")
      (description "IND_0805")
      (libsource (lib "*") (part "IND_0805"))
    )
    (comp (ref "L27")
      (value "15uH")
      (footprint "IND_0805")
      (description "IND_0805")
      (libsource (lib "*") (part "IND_0805"))
    )
    (comp (ref "L28")
      (value "15uH")
      (footprint "IND_0805")
      (description "IND_0805")
      (libsource (lib "*") (part "IND_0805"))
    )
    (comp (ref "L29")
      (value "6.8uH")
      (footprint "IND_0805")
      (description "IND_0805")
      (libsource (lib "*") (part "IND_0805"))
    )
    (comp (ref "L30")
      (value "4.7uH")
      (footprint "IND_0805")
      (description "IND_0805")
      (libsource (lib "*") (part "IND_0805"))
    )
    (comp (ref "L31")
      (value "6.8uH")
      (footprint "IND_0805")
      (description "IND_0805")
      (libsource (lib "*") (part "IND_0805"))
    )
    (comp (ref "L32")
      (value "33uH")
      (footprint "IND_0805")
      (description "IND_0805")
      (libsource (lib "*") (part "IND_0805"))
    )
    (comp (ref "L33")
      (value "33uH")
      (footprint "IND_0805")
      (description "IND_0805")
      (libsource (lib "*") (part "IND_0805"))
    )
    (comp (ref "L34")
      (value "8.2nH")
      (footprint "IND_0805")
      (description "IND_0805")
      (libsource (lib "*") (part "IND_0805"))
    )
    (comp (ref "L35")
      (value "8.2nH")
      (footprint "IND_0805")
      (description "IND_0805")
      (libsource (lib "*") (part "IND_0805"))
    )
    (comp (ref "L36")
      (value "8.2nH")
      (footprint "IND_0805")
      (description "IND_0805")
      (libsource (lib "*") (part "IND_0805"))
    )
    (comp (ref "L37")
      (value "10uH")
      (footprint "IND_FERRITE_CORE")
      (description "Inductor")
      (fields (field (name "Comment") "IND_FERRITE_CORE"))
      (libsource (lib "*") (part "IND_FERRITE_CORE"))
    )
    (comp (ref "L38")
      (value "10uH")
      (footprint "IND_FERRITE_CORE")
      (description "Inductor")
      (fields (field (name "Comment") "IND_FERRITE_CORE"))
      (libsource (lib "*") (part "IND_FERRITE_CORE"))
    )
    (comp (ref "L39")
      (value "FB")
      (footprint "IND_FERRITE_BEAD")
      (description "Ferrite bead on conductor")
      (fields (field (name "Comment") "IND_FERRITE_BEAD"))
      (libsource (lib "*") (part "IND_FERRITE_BEAD"))
    )
    (comp (ref "L40")
      (value "150nH")
      (footprint "IND_0805")
      (description "IND_0805")
      (libsource (lib "*") (part "IND_0805"))
    )
    (comp (ref "L41")
      (value "150nH")
      (footprint "IND_0805")
      (description "IND_0805")
      (libsource (lib "*") (part "IND_0805"))
    )
    (comp (ref "L42")
      (value "330nH")
      (footprint "IND_0805")
      (description "IND_0805")
      (libsource (lib "*") (part "IND_0805"))
    )
    (comp (ref "L43")
      (value "10uH")
      (footprint "IND_FERRITE_CORE")
      (description "Inductor")
      (fields (field (name "Comment") "IND_FERRITE_CORE"))
      (libsource (lib "*") (part "IND_FERRITE_CORE"))
    )
    (comp (ref "L44")
      (value "169nH")
      (footprint "IND_FERRITE_CORE_1")
      (description "Inductor")
      (fields (field (name "Comment") "IND_FERRITE_CORE"))
      (libsource (lib "*") (part "IND_FERRITE_CORE"))
    )
    (comp (ref "L45")
      (value "169nH")
      (footprint "IND_FERRITE_CORE_1")
      (description "Inductor")
      (fields (field (name "Comment") "IND_FERRITE_CORE"))
      (libsource (lib "*") (part "IND_FERRITE_CORE"))
    )
    (comp (ref "L46")
      (value "220nH")
      (footprint "IND_1206")
      (description "IND_1206")
      (libsource (lib "*") (part "IND_1206"))
    )
    (comp (ref "Q1") (value "RD07MVS1") (footprint "RD07MVS1") (libsource (lib "*") (part "RD07MVS1")))
    (comp (ref "Q2")
      (value "IRLML9301")
      (footprint "SOT23")
      (description "MOSFET")
      (fields (field (name "Comment") "MOSFET_ENH_PD"))
      (libsource (lib "*") (part "MOSFET_ENH_PD"))
    )
    (comp (ref "Q3") (value "RD07MVS1") (footprint "RD07MVS1") (libsource (lib "*") (part "RD07MVS1")))
    (comp (ref "Q4")
      (value "PGA-103+")
      (footprint "SOT89")
      (description "MOSFET")
      (libsource (lib "*") (part "PGA-103+"))
    )
    (comp (ref "R1")
      (value "56")
      (footprint "RES_0805")
      (description "RES_0805")
      (libsource (lib "*") (part "RES_0805"))
    )
    (comp (ref "R2") (value "RES_0805") (footprint "RES_0805") (libsource (lib "*") (part "RES_0805")))
    (comp (ref "R3")
      (value "56")
      (footprint "RES_0805")
      (description "RES_0805")
      (libsource (lib "*") (part "RES_0805"))
    )
    (comp (ref "R4") (value "RES_0805") (footprint "RES_0805") (libsource (lib "*") (part "RES_0805")))
    (comp (ref "R5")
      (value "56")
      (footprint "RES_0805")
      (description "RES_0805")
      (libsource (lib "*") (part "RES_0805"))
    )
    (comp (ref "R6")
      (value "120")
      (footprint "RES_0805")
      (description "RES_0805")
      (libsource (lib "*") (part "RES_0805"))
    )
    (comp (ref "R7")
      (value "56")
      (footprint "RES_0805")
      (description "RES_0805")
      (libsource (lib "*") (part "RES_0805"))
    )
    (comp (ref "R8")
      (value "120")
      (footprint "RES_0805")
      (description "RES_0805")
      (libsource (lib "*") (part "RES_0805"))
    )
    (comp (ref "R9")
      (value "56")
      (footprint "RES_0805")
      (description "RES_0805")
      (libsource (lib "*") (part "RES_0805"))
    )
    (comp (ref "R10")
      (value "120")
      (footprint "RES_0805")
      (description "RES_0805")
      (libsource (lib "*") (part "RES_0805"))
    )
    (comp (ref "R11")
      (value "56")
      (footprint "RES_0805")
      (description "RES_0805")
      (libsource (lib "*") (part "RES_0805"))
    )
    (comp (ref "R12")
      (value "120")
      (footprint "RES_0805")
      (description "RES_0805")
      (libsource (lib "*") (part "RES_0805"))
    )
    (comp (ref "R13")
      (value "56")
      (footprint "RES_0805")
      (description "RES_0805")
      (libsource (lib "*") (part "RES_0805"))
    )
    (comp (ref "R14")
      (value "120")
      (footprint "RES_0805")
      (description "RES_0805")
      (libsource (lib "*") (part "RES_0805"))
    )
    (comp (ref "R15")
      (value "56")
      (footprint "RES_0805")
      (description "RES_0805")
      (libsource (lib "*") (part "RES_0805"))
    )
    (comp (ref "R16")
      (value "120")
      (footprint "RES_0805")
      (description "RES_0805")
      (libsource (lib "*") (part "RES_0805"))
    )
    (comp (ref "R17")
      (value "220")
      (footprint "RES_0805")
      (description "RES_0805")
      (libsource (lib "*") (part "RES_0805"))
    )
    (comp (ref "R18")
      (value "220")
      (footprint "RES_0805")
      (description "RES_0805")
      (libsource (lib "*") (part "RES_0805"))
    )
    (comp (ref "R19")
      (value "10k")
      (footprint "RES_0805")
      (description "RES_0805")
      (libsource (lib "*") (part "RES_0805"))
    )
    (comp (ref "R20")
      (value "10k")
      (footprint "RES_0805")
      (description "RES_0805")
      (libsource (lib "*") (part "RES_0805"))
    )
    (comp (ref "R21")
      (value "10k")
      (footprint "RES_0805")
      (description "RES_0805")
      (libsource (lib "*") (part "RES_0805"))
    )
    (comp (ref "R22")
      (value "10k")
      (footprint "RES_0805")
      (description "RES_0805")
      (libsource (lib "*") (part "RES_0805"))
    )
    (comp (ref "R23")
      (value "10k")
      (footprint "RES_0805")
      (description "RES_0805")
      (libsource (lib "*") (part "RES_0805"))
    )
    (comp (ref "R24")
      (value "10k")
      (footprint "RES_0805")
      (description "RES_0805")
      (libsource (lib "*") (part "RES_0805"))
    )
    (comp (ref "R25")
      (value "10k")
      (footprint "RES_0805")
      (description "RES_0805")
      (libsource (lib "*") (part "RES_0805"))
    )
    (comp (ref "R26")
      (value "10k")
      (footprint "RES_0805")
      (description "RES_0805")
      (libsource (lib "*") (part "RES_0805"))
    )
    (comp (ref "R27")
      (value "15")
      (footprint "RES_0805")
      (description "RES_0805")
      (libsource (lib "*") (part "RES_0805"))
    )
    (comp (ref "R28")
      (value "39")
      (footprint "RES_0805")
      (description "RES_0805")
      (libsource (lib "*") (part "RES_0805"))
    )
    (comp (ref "R29")
      (value "15")
      (footprint "RES_0805")
      (description "RES_0805")
      (libsource (lib "*") (part "RES_0805"))
    )
    (comp (ref "R30")
      (value "68")
      (footprint "RES_0805")
      (description "RES_0805")
      (libsource (lib "*") (part "RES_0805"))
    )
    (comp (ref "R31")
      (value "68")
      (footprint "RES_0805")
      (description "RES_0805")
      (libsource (lib "*") (part "RES_0805"))
    )
    (comp (ref "R32")
      (value "560")
      (footprint "RES_0805")
      (description "RES_0805")
      (libsource (lib "*") (part "RES_0805"))
    )
    (comp (ref "R33")
      (value "5.6")
      (footprint "RES_0805")
      (description "RES_0805")
      (libsource (lib "*") (part "RES_0805"))
    )
    (comp (ref "R34")
      (value "5.6")
      (footprint "RES_1206")
      (description "RES_1206")
      (libsource (lib "*") (part "RES_1206"))
    )
    (comp (ref "R35")
      (value "1k")
      (footprint "RES_0805")
      (description "RES_0805")
      (libsource (lib "*") (part "RES_0805"))
    )
    (comp (ref "R36")
      (value "510")
      (footprint "RES_0805")
      (description "RES_0805")
      (libsource (lib "*") (part "RES_0805"))
    )
    (comp (ref "R37")
      (value "5.6")
      (footprint "RES_0805")
      (description "RES_0805")
      (libsource (lib "*") (part "RES_0805"))
    )
    (comp (ref "R38")
      (value "5.6")
      (footprint "RES_1206")
      (description "RES_1206")
      (libsource (lib "*") (part "RES_1206"))
    )
    (comp (ref "R39")
      (value "18")
      (footprint "RES_1206")
      (description "RES_1206")
      (libsource (lib "*") (part "RES_1206"))
    )
    (comp (ref "R40")
      (value "1k")
      (footprint "306J")
      (description "306J")
      (libsource (lib "*") (part "306J"))
    )
    (comp (ref "R41")
      (value "10k")
      (footprint "RES_0805")
      (description "RES_0805")
      (libsource (lib "*") (part "RES_0805"))
    )
    (comp (ref "R42")
      (value "1k")
      (footprint "RES_0805")
      (description "RES_0805")
      (libsource (lib "*") (part "RES_0805"))
    )
    (comp (ref "R43")
      (value "1k")
      (footprint "RES_0805")
      (description "RES_0805")
      (libsource (lib "*") (part "RES_0805"))
    )
    (comp (ref "R44")
      (value "56")
      (footprint "RES_0805")
      (description "RES_0805")
      (libsource (lib "*") (part "RES_0805"))
    )
    (comp (ref "R45")
      (value "10k")
      (footprint "RES_0805")
      (description "RES_0805")
      (libsource (lib "*") (part "RES_0805"))
    )
    (comp (ref "R46")
      (value "560")
      (footprint "RES_0805")
      (description "RES_0805")
      (libsource (lib "*") (part "RES_0805"))
    )
    (comp (ref "R47")
      (value "300")
      (footprint "RES_1206")
      (description "RES_1206")
      (libsource (lib "*") (part "RES_1206"))
    )
    (comp (ref "R48")
      (value "300")
      (footprint "RES_1206")
      (description "RES_1206")
      (libsource (lib "*") (part "RES_1206"))
    )
    (comp (ref "R49")
      (value "0")
      (footprint "RES_0805")
      (description "RES_0805")
      (libsource (lib "*") (part "RES_0805"))
    )
    (comp (ref "R50")
      (value "0")
      (footprint "RES_0805")
      (description "RES_0805")
      (libsource (lib "*") (part "RES_0805"))
    )
    (comp (ref "R51")
      (value "TERMO 1K")
      (footprint "RES")
      (description "RES")
      (libsource (lib "*") (part "RES"))
    )
    (comp (ref "R52")
      (value "200")
      (footprint "RES_0805")
      (description "RES_0805")
      (libsource (lib "*") (part "RES_0805"))
    )
    (comp (ref "R53")
      (value "1.2k")
      (footprint "RES_0805")
      (description "RES_0805")
      (libsource (lib "*") (part "RES_0805"))
    )
    (comp (ref "R54")
      (value "510")
      (footprint "RES_0805")
      (description "RES_0805")
      (libsource (lib "*") (part "RES_0805"))
    )
    (comp (ref "R55")
      (value "50")
      (footprint "RES_1206")
      (description "RES_1206")
      (libsource (lib "*") (part "RES_1206"))
    )
    (comp (ref "R56")
      (value "50")
      (footprint "RES_1206")
      (description "RES_1206")
      (libsource (lib "*") (part "RES_1206"))
    )
    (comp (ref "T1")
      (value "1:4 ADT4-6T")
      (footprint "TRANSF_ACORE2")
      (description "Transformer")
      (fields (field (name "Comment") "TRANSF_ACORE2"))
      (libsource (lib "") (part "TRANSF_ACORE2_1"))
    )
    (comp (ref "T2")
      (value "1:4 ADT4-6T")
      (footprint "TRANSF_ACORE2_1")
      (description "Transformer")
      (fields (field (name "Comment") "TRANSF_ACORE2"))
      (libsource (lib "") (part "TRANSF_ACORE2_2"))
    )
    (comp (ref "T4")
      (value "Balun 4turns rg-178 on binocle")
      (footprint "TRANSF_ICORE")
      (description "Transformer")
      (fields (field (name "Comment") "TRANSF_ICORE"))
      (libsource (lib "*") (part "TRANSF_ICORE"))
    )
    (comp (ref "T5")
      (value "TRANSF_ACORE2")
      (footprint "TRANSF_ACORE2_2")
      (description "Transformer")
      (libsource (lib "*") (part "TRANSF_ACORE2"))
    )
    (comp (ref "TSWR")
      (value "SWR_TANDEM_MATCH")
      (footprint "SWR_TANDEM_MATCH")
      (libsource (lib "*") (part "SWR_TANDEM_MATCH"))
    )
    (comp (ref "U1")
      (value "SN74HC595D")
      (footprint "D0016A_L")
      (description "8-Bit Shift Registers With 3-State Output Registers, D0016A, TUBE")
      (fields
        (field (name "GENERIC PART NUMBER") "SN74HC595")
        (field (name "MANUFACTURER") "Texas Instruments")
      )
      (libsource (lib "Altium Content Vault") (part "TI-SN74XHCT595X_SN74LV595A-16"))
    )
    (comp (ref "U2") (value "ULN2003BDR") (footprint "ULN2003BDR") (libsource (lib "*") (part "ULN2003BDR")))
    (comp (ref "U3")
      (value "SN74HC595D")
      (footprint "D0016A_L")
      (description "8-Bit Shift Registers With 3-State Output Registers, D0016A, TUBE")
      (fields
        (field (name "GENERIC PART NUMBER") "SN74HC595")
        (field (name "MANUFACTURER") "Texas Instruments")
      )
      (libsource (lib "Altium Content Vault") (part "TI-SN74XHCT595X_SN74LV595A-16"))
    )
    (comp (ref "U4") (value "ULN2003BDR") (footprint "ULN2003BDR") (libsource (lib "*") (part "ULN2003BDR")))
    (comp (ref "U5")
      (value "LT1117-ADJ")
      (footprint "LT1117IST-ADJ")
      (description "LT1117IST-ADJ")
      (libsource (lib "*") (part "LT1117IST-ADJ"))
    )
    (comp (ref "U6") (value "AMS1117-5") (footprint "AMS1117-5") (libsource (lib "*") (part "AMS1117-5")))
    (comp (ref "U7")
      (value "SN74HC595D")
      (footprint "D0016A_L")
      (description "8-Bit Shift Registers With 3-State Output Registers, D0016A, TUBE")
      (fields
        (field (name "GENERIC PART NUMBER") "SN74HC595")
        (field (name "MANUFACTURER") "Texas Instruments")
      )
      (libsource (lib "Altium Content Vault") (part "TI-SN74XHCT595X_SN74LV595A-16"))
    )
    (comp (ref "U8") (value "ULN2003BDR") (footprint "ULN2003BDR") (libsource (lib "*") (part "ULN2003BDR")))
  )
  (nets
    (net (code "1") (name "+3V3") (class "Default")
      (node (ref "J4") (pin "1") (pinfunction "3.3V_1") (pintype "passive"))
      (node (ref "R35") (pin "1") (pinfunction "1_1") (pintype "passive"))
      (node (ref "U1") (pin "10") (pinfunction "~{SRCLR}_10") (pintype "input"))
      (node (ref "U1") (pin "16") (pinfunction "VCC_16") (pintype "power_in"))
      (node (ref "U3") (pin "10") (pinfunction "~{SRCLR}_10") (pintype "input"))
      (node (ref "U3") (pin "16") (pinfunction "VCC_16") (pintype "power_in"))
      (node (ref "U7") (pin "10") (pinfunction "~{SRCLR}_10") (pintype "input"))
      (node (ref "U7") (pin "16") (pinfunction "VCC_16") (pintype "power_in"))
    )
    (net (code "2") (name "+12") (class "Default")
      (node (ref "C115") (pin "2") (pinfunction "2_2") (pintype "passive"))
      (node (ref "C118") (pin "2") (pinfunction "2_2") (pintype "passive"))
      (node (ref "C119") (pin "1") (pinfunction "PLUS_1") (pintype "passive"))
      (node (ref "C129") (pin "1") (pinfunction "PLUS_1") (pintype "passive"))
      (node (ref "C130") (pin "2") (pinfunction "2_2") (pintype "passive"))
      (node (ref "D18") (pin "1") (pinfunction "K_1") (pintype "passive"))
      (node (ref "D20") (pin "1") (pinfunction "K_1") (pintype "passive"))
      (node (ref "D21") (pin "1") (pinfunction "K_1") (pintype "passive"))
      (node (ref "D26") (pin "1") (pinfunction "K_1") (pintype "passive"))
      (node (ref "D3") (pin "1") (pinfunction "K_1") (pintype "passive"))
      (node (ref "FAN_OUT") (pin "1") (pinfunction "+_1") (pintype "passive"))
      (node (ref "J8") (pin "2") (pinfunction "+_2") (pintype "passive"))
      (node (ref "K1") (pin "1") (pinfunction "1_1") (pintype "passive"))
      (node (ref "K2") (pin "1") (pinfunction "+_1") (pintype "passive"))
      (node (ref "K3") (pin "1") (pinfunction "1_1") (pintype "passive"))
      (node (ref "K4") (pin "1") (pinfunction "1_1") (pintype "passive"))
      (node (ref "K5") (pin "1") (pinfunction "1_1") (pintype "passive"))
      (node (ref "L39") (pin "2") (pinfunction "2_2") (pintype "passive"))
      (node (ref "L43") (pin "2") (pinfunction "B_2") (pintype "passive"))
      (node (ref "Q2") (pin "2") (pinfunction "S_2") (pintype "passive"))
      (node (ref "R41") (pin "2") (pinfunction "2_2") (pintype "passive"))
      (node (ref "U2") (pin "9") (pinfunction "COM_9") (pintype "passive"))
      (node (ref "U4") (pin "9") (pinfunction "COM_9") (pintype "passive"))
      (node (ref "U6") (pin "3") (pinfunction "IN_3") (pintype "passive"))
      (node (ref "U8") (pin "9") (pinfunction "COM_9") (pintype "passive"))
    )
    (net (code "3") (name "/NetK4_2") (class "Default")
      (node (ref "K4") (pin "2") (pinfunction "2_2") (pintype "passive"))
      (node (ref "T1") (pin "10") (pinfunction "0_10") (pintype "passive"))
      (node (ref "T1") (pin "6") (pinfunction "P2_6") (pintype "passive"))
    )
    (net (code "4") (name "/Сеть 10") (class "Default")
      (node (ref "C103") (pin "1") (pinfunction "1_1") (pintype "passive"))
      (node (ref "C110") (pin "2") (pinfunction "2_2") (pintype "passive"))
      (node (ref "K5") (pin "7") (pinfunction "7_7") (pintype "passive"))
      (node (ref "L42") (pin "2") (pinfunction "2_2") (pintype "passive"))
    )
    (net (code "5") (name "/Сеть 20") (class "Default")
      (node (ref "D22") (pin "2") (pinfunction "A_2") (pintype "passive"))
      (node (ref "R55") (pin "1") (pinfunction "1_1") (pintype "passive"))
      (node (ref "TSWR") (pin "4") (pinfunction "4_4") (pintype "passive"))
      (node (ref "TSWR") (pin "6") (pinfunction "6_6") (pintype "passive"))
    )
    (net (code "6") (name "/Сеть 21") (class "Default")
      (node (ref "Q3") (pin "3") (pinfunction "G_3") (pintype "passive"))
      (node (ref "R38") (pin "2") (pinfunction "2_2") (pintype "passive"))
      (node (ref "R46") (pin "1") (pinfunction "1_1") (pintype "passive"))
    )
    (net (code "7") (name "/Сеть 22") (class "Default")
      (node (ref "D23") (pin "2") (pinfunction "A_2") (pintype "passive"))
      (node (ref "R40") (pin "2") (pinfunction "W_2") (pintype "passive"))
    )
    (net (code "8") (name "/Сеть 23") (class "Default")
      (node (ref "Q1") (pin "3") (pinfunction "G_3") (pintype "passive"))
      (node (ref "R32") (pin "1") (pinfunction "1_1") (pintype "passive"))
      (node (ref "R34") (pin "2") (pinfunction "2_2") (pintype "passive"))
    )
    (net (code "9") (name "/Сеть 24") (class "Default")
      (node (ref "C111") (pin "1") (pinfunction "1_1") (pintype "passive"))
      (node (ref "R32") (pin "2") (pinfunction "2_2") (pintype "passive"))
    )
    (net (code "10") (name "/Сеть 26") (class "Default")
      (node (ref "C111") (pin "2") (pinfunction "2_2") (pintype "passive"))
      (node (ref "C91") (pin "1") (pinfunction "1_1") (pintype "passive"))
      (node (ref "C92") (pin "1") (pinfunction "1_1") (pintype "passive"))
      (node (ref "L37") (pin "1") (pinfunction "A_1") (pintype "passive"))
      (node (ref "Q1") (pin "1") (pinfunction "D_1") (pintype "passive"))
      (node (ref "R48") (pin "2") (pinfunction "2_2") (pintype "passive"))
    )
    (net (code "11") (name "/Сеть 27") (class "Default")
      (node (ref "D23") (pin "1") (pinfunction "K_1") (pintype "passive"))
      (node (ref "R44") (pin "1") (pinfunction "1_1") (pintype "passive"))
      (node (ref "R45") (pin "2") (pinfunction "2_2") (pintype "passive"))
    )
    (net (code "12") (name "/Сеть 31") (class "Default")
      (node (ref "C128") (pin "1") (pinfunction "1_1") (pintype "passive"))
      (node (ref "R40") (pin "3") (pinfunction "CW_3") (pintype "passive"))
      (node (ref "R52") (pin "1") (pinfunction "1_1") (pintype "passive"))
      (node (ref "U5") (pin "2") (pinfunction "OUT_2") (pintype "passive"))
      (node (ref "U5") (pin "4") (pinfunction "Vout_4") (pintype "passive"))
    )
    (net (code "13") (name "/Сеть 33") (class "Default")
      (node (ref "D19") (pin "2") (pinfunction "A_2") (pintype "passive"))
      (node (ref "R56") (pin "1") (pinfunction "1_1") (pintype "passive"))
      (node (ref "TSWR") (pin "3") (pinfunction "3_3") (pintype "passive"))
    )
    (net (code "14") (name "/Сеть 34") (class "Default")
      (node (ref "C93") (pin "2") (pinfunction "2_2") (pintype "passive"))
      (node (ref "C94") (pin "2") (pinfunction "2_2") (pintype "passive"))
      (node (ref "T4") (pin "3") (pinfunction "S1_3") (pintype "passive"))
    )
    (net (code "15") (name "/Сеть 35") (class "Default")
      (node (ref "C113") (pin "1") (pinfunction "1_1") (pintype "passive"))
      (node (ref "D19") (pin "1") (pinfunction "K_1") (pintype "passive"))
      (node (ref "R49") (pin "1") (pinfunction "1_1") (pintype "passive"))
    )
    (net (code "16") (name "/Сеть 42") (class "Default")
      (node (ref "C112") (pin "2") (pinfunction "2_2") (pintype "passive"))
      (node (ref "K3") (pin "4") (pinfunction "4_4") (pintype "passive"))
    )
    (net (code "17") (name "/Сеть 43") (class "Default")
      (node (ref "U7") (pin "1") (pinfunction "QB_1") (pintype "tri_state"))
      (node (ref "U8") (pin "4") (pinfunction "4B_4") (pintype "passive"))
    )
    (net (code "18") (name "/Сеть 44") (class "Default")
      (node (ref "C112") (pin "1") (pinfunction "1_1") (pintype "passive"))
      (node (ref "Q4") (pin "1") (pinfunction "G_1") (pintype "passive"))
    )
    (net (code "19") (name "/Сеть 46") (class "Default")
      (node (ref "K4") (pin "7") (pinfunction "7_7") (pintype "passive"))
      (node (ref "T2") (pin "11") (pinfunction "0_11") (pintype "passive"))
      (node (ref "T2") (pin "4") (pinfunction "S3_4") (pintype "passive"))
    )
    (net (code "20") (name "/Сеть 47") (class "Default")
      (node (ref "U7") (pin "3") (pinfunction "QD_3") (pintype "tri_state"))
      (node (ref "U8") (pin "2") (pinfunction "2B_2") (pintype "passive"))
    )
    (net (code "21") (name "/Сеть 84") (class "Default")
      (node (ref "C1") (pin "2") (pinfunction "2_2") (pintype "passive"))
      (node (ref "C2") (pin "2") (pinfunction "2_2") (pintype "passive"))
      (node (ref "L1") (pin "1") (pinfunction "1_1") (pintype "passive"))
      (node (ref "R1") (pin "2") (pinfunction "2_2") (pintype "passive"))
      (node (ref "R2") (pin "1") (pinfunction "1_1") (pintype "passive"))
    )
    (net (code "22") (name "/Сеть 85") (class "Default")
      (node (ref "C3") (pin "2") (pinfunction "2_2") (pintype "passive"))
      (node (ref "C4") (pin "2") (pinfunction "2_2") (pintype "passive"))
      (node (ref "L3") (pin "1") (pinfunction "1_1") (pintype "passive"))
      (node (ref "R2") (pin "2") (pinfunction "2_2") (pintype "passive"))
    )
    (net (code "23") (name "/Сеть 88") (class "Default")
      (node (ref "C5") (pin "2") (pinfunction "2_2") (pintype "passive"))
      (node (ref "D1") (pin "1") (pinfunction "(C)_1") (pintype "passive"))
      (node (ref "L1") (pin "2") (pinfunction "2_2") (pintype "passive"))
    )
    (net (code "24") (name "/Сеть 89") (class "Default")
      (node (ref "C5") (pin "1") (pinfunction "1_1") (pintype "passive"))
      (node (ref "C6") (pin "2") (pinfunction "2_2") (pintype "passive"))
      (node (ref "L2") (pin "2") (pinfunction "2_2") (pintype "passive"))
    )
    (net (code "25") (name "/Сеть 90") (class "Default")
      (node (ref "C6") (pin "1") (pinfunction "1_1") (pintype "passive"))
      (node (ref "D2") (pin "1") (pinfunction "(C)_1") (pintype "passive"))
      (node (ref "L3") (pin "2") (pinfunction "2_2") (pintype "passive"))
    )
    (net (code "26") (name "/Сеть 91") (class "Default")
      (node (ref "C11") (pin "2") (pinfunction "2_2") (pintype "passive"))
      (node (ref "L7") (pin "2") (pinfunction "2_2") (pintype "passive"))
    )
    (net (code "27") (name "/Сеть 92") (class "Default")
      (node (ref "C12") (pin "2") (pinfunction "2_2") (pintype "passive"))
      (node (ref "L8") (pin "2") (pinfunction "2_2") (pintype "passive"))
    )
    (net (code "28") (name "/Сеть 93") (class "Default")
      (node (ref "C7") (pin "2") (pinfunction "2_2") (pintype "passive"))
      (node (ref "C8") (pin "2") (pinfunction "2_2") (pintype "passive"))
      (node (ref "L4") (pin "1") (pinfunction "1_1") (pintype "passive"))
      (node (ref "R3") (pin "2") (pinfunction "2_2") (pintype "passive"))
      (node (ref "R4") (pin "1") (pinfunction "1_1") (pintype "passive"))
    )
    (net (code "29") (name "/Сеть 94") (class "Default")
      (node (ref "C10") (pin "2") (pinfunction "2_2") (pintype "passive"))
      (node (ref "C15") (pin "1") (pinfunction "1_1") (pintype "passive"))
      (node (ref "C9") (pin "2") (pinfunction "2_2") (pintype "passive"))
      (node (ref "L6") (pin "1") (pinfunction "1_1") (pintype "passive"))
      (node (ref "R4") (pin "2") (pinfunction "2_2") (pintype "passive"))
    )
    (net (code "30") (name "/Сеть 95") (class "Default")
      (node (ref "C12") (pin "1") (pinfunction "1_1") (pintype "passive"))
      (node (ref "C15") (pin "2") (pinfunction "2_2") (pintype "passive"))
      (node (ref "D5") (pin "1") (pinfunction "(C)_1") (pintype "passive"))
      (node (ref "L6") (pin "2") (pinfunction "2_2") (pintype "passive"))
    )
    (net (code "31") (name "/Сеть 96") (class "Default")
      (node (ref "C11") (pin "1") (pinfunction "1_1") (pintype "passive"))
      (node (ref "C14") (pin "2") (pinfunction "2_2") (pintype "passive"))
      (node (ref "L5") (pin "2") (pinfunction "2_2") (pintype "passive"))
      (node (ref "L8") (pin "1") (pinfunction "1_1") (pintype "passive"))
    )
    (net (code "32") (name "/Сеть 101") (class "Default")
      (node (ref "C22") (pin "2") (pinfunction "2_2") (pintype "passive"))
      (node (ref "C25") (pin "2") (pinfunction "2_2") (pintype "passive"))
      (node (ref "D6") (pin "1") (pinfunction "(C)_1") (pintype "passive"))
      (node (ref "L12") (pin "1") (pinfunction "1_1") (pintype "passive"))
      (node (ref "L9") (pin "2") (pinfunction "2_2") (pintype "passive"))
    )
    (net (code "33") (name "/Сеть 102") (class "Default")
      (node (ref "C16") (pin "2") (pinfunction "2_2") (pintype "passive"))
      (node (ref "C17") (pin "2") (pinfunction "2_2") (pintype "passive"))
      (node (ref "L9") (pin "1") (pinfunction "1_1") (pintype "passive"))
      (node (ref "R5") (pin "2") (pinfunction "2_2") (pintype "passive"))
      (node (ref "R6") (pin "1") (pinfunction "1_1") (pintype "passive"))
    )
    (net (code "34") (name "/Сеть 103") (class "Default")
      (node (ref "C18") (pin "2") (pinfunction "2_2") (pintype "passive"))
      (node (ref "C19") (pin "2") (pinfunction "2_2") (pintype "passive"))
      (node (ref "C24") (pin "1") (pinfunction "1_1") (pintype "passive"))
      (node (ref "C27") (pin "1") (pinfunction "1_1") (pintype "passive"))
      (node (ref "L11") (pin "1") (pinfunction "1_1") (pintype "passive"))
      (node (ref "R6") (pin "2") (pinfunction "2_2") (pintype "passive"))
    )
    (net (code "35") (name "/Сеть 104") (class "Default")
      (node (ref "C20") (pin "2") (pinfunction "2_2") (pintype "passive"))
      (node (ref "L12") (pin "2") (pinfunction "2_2") (pintype "passive"))
    )
    (net (code "36") (name "/Сеть 105") (class "Default")
      (node (ref "C20") (pin "1") (pinfunction "1_1") (pintype "passive"))
      (node (ref "C23") (pin "2") (pinfunction "2_2") (pintype "passive"))
      (node (ref "C26") (pin "2") (pinfunction "2_2") (pintype "passive"))
      (node (ref "L10") (pin "2") (pinfunction "2_2") (pintype "passive"))
      (node (ref "L13") (pin "1") (pinfunction "1_1") (pintype "passive"))
    )
    (net (code "37") (name "/Сеть 106") (class "Default")
      (node (ref "C21") (pin "1") (pinfunction "1_1") (pintype "passive"))
      (node (ref "C24") (pin "2") (pinfunction "2_2") (pintype "passive"))
      (node (ref "C27") (pin "2") (pinfunction "2_2") (pintype "passive"))
      (node (ref "D7") (pin "1") (pinfunction "(C)_1") (pintype "passive"))
      (node (ref "L11") (pin "2") (pinfunction "2_2") (pintype "passive"))
    )
    (net (code "38") (name "/Сеть 107") (class "Default")
      (node (ref "C21") (pin "2") (pinfunction "2_2") (pintype "passive"))
      (node (ref "L13") (pin "2") (pinfunction "2_2") (pintype "passive"))
    )
    (net (code "39") (name "/Сеть 108") (class "Default")
      (node (ref "U7") (pin "2") (pinfunction "QC_2") (pintype "tri_state"))
      (node (ref "U8") (pin "3") (pinfunction "3B_3") (pintype "passive"))
    )
    (net (code "40") (name "/Сеть 109") (class "Default")
      (node (ref "C34") (pin "2") (pinfunction "2_2") (pintype "passive"))
      (node (ref "C37") (pin "2") (pinfunction "2_2") (pintype "passive"))
      (node (ref "D8") (pin "1") (pinfunction "(C)_1") (pintype "passive"))
      (node (ref "L14") (pin "2") (pinfunction "2_2") (pintype "passive"))
      (node (ref "L17") (pin "1") (pinfunction "1_1") (pintype "passive"))
    )
    (net (code "41") (name "/Сеть 110") (class "Default")
      (node (ref "C28") (pin "2") (pinfunction "2_2") (pintype "passive"))
      (node (ref "C29") (pin "2") (pinfunction "2_2") (pintype "passive"))
      (node (ref "L14") (pin "1") (pinfunction "1_1") (pintype "passive"))
      (node (ref "R7") (pin "2") (pinfunction "2_2") (pintype "passive"))
      (node (ref "R8") (pin "1") (pinfunction "1_1") (pintype "passive"))
    )
    (net (code "42") (name "/Сеть 111") (class "Default")
      (node (ref "C30") (pin "2") (pinfunction "2_2") (pintype "passive"))
      (node (ref "C31") (pin "2") (pinfunction "2_2") (pintype "passive"))
      (node (ref "C36") (pin "1") (pinfunction "1_1") (pintype "passive"))
      (node (ref "C39") (pin "1") (pinfunction "1_1") (pintype "passive"))
      (node (ref "L16") (pin "1") (pinfunction "1_1") (pintype "passive"))
      (node (ref "R8") (pin "2") (pinfunction "2_2") (pintype "passive"))
    )
    (net (code "43") (name "/Сеть 112") (class "Default")
      (node (ref "J1") (pin "5") (pinfunction "CON_5") (pintype "passive"))
      (node (ref "K2") (pin "3") (pinfunction "P_3") (pintype "passive"))
    )
    (net (code "44") (name "/Сеть 114") (class "Default")
      (node (ref "C32") (pin "2") (pinfunction "2_2") (pintype "passive"))
      (node (ref "L17") (pin "2") (pinfunction "2_2") (pintype "passive"))
    )
    (net (code "45") (name "/Сеть 116") (class "Default")
      (node (ref "C32") (pin "1") (pinfunction "1_1") (pintype "passive"))
      (node (ref "C35") (pin "2") (pinfunction "2_2") (pintype "passive"))
      (node (ref "L15") (pin "2") (pinfunction "2_2") (pintype "passive"))
      (node (ref "L18") (pin "1") (pinfunction "1_1") (pintype "passive"))
    )
    (net (code "46") (name "/Сеть 117") (class "Default")
      (node (ref "C33") (pin "1") (pinfunction "1_1") (pintype "passive"))
      (node (ref "C36") (pin "2") (pinfunction "2_2") (pintype "passive"))
      (node (ref "C39") (pin "2") (pinfunction "2_2") (pintype "passive"))
      (node (ref "D9") (pin "1") (pinfunction "(C)_1") (pintype "passive"))
      (node (ref "L16") (pin "2") (pinfunction "2_2") (pintype "passive"))
    )
    (net (code "47") (name "/Сеть 118") (class "Default")
      (node (ref "C33") (pin "2") (pinfunction "2_2") (pintype "passive"))
      (node (ref "L18") (pin "2") (pinfunction "2_2") (pintype "passive"))
    )
    (net (code "48") (name "/Сеть 120") (class "Default")
      (node (ref "C46") (pin "2") (pinfunction "2_2") (pintype "passive"))
      (node (ref "C49") (pin "2") (pinfunction "2_2") (pintype "passive"))
      (node (ref "D10") (pin "1") (pinfunction "(C)_1") (pintype "passive"))
      (node (ref "L19") (pin "2") (pinfunction "2_2") (pintype "passive"))
      (node (ref "L22") (pin "1") (pinfunction "1_1") (pintype "passive"))
    )
    (net (code "49") (name "/Сеть 121") (class "Default")
      (node (ref "C40") (pin "2") (pinfunction "2_2") (pintype "passive"))
      (node (ref "C41") (pin "2") (pinfunction "2_2") (pintype "passive"))
      (node (ref "L19") (pin "1") (pinfunction "1_1") (pintype "passive"))
      (node (ref "R10") (pin "1") (pinfunction "1_1") (pintype "passive"))
      (node (ref "R9") (pin "2") (pinfunction "2_2") (pintype "passive"))
    )
    (net (code "50") (name "/Сеть 122") (class "Default")
      (node (ref "C42") (pin "2") (pinfunction "2_2") (pintype "passive"))
      (node (ref "C43") (pin "2") (pinfunction "2_2") (pintype "passive"))
      (node (ref "C48") (pin "1") (pinfunction "1_1") (pintype "passive"))
      (node (ref "C51") (pin "1") (pinfunction "1_1") (pintype "passive"))
      (node (ref "L21") (pin "1") (pinfunction "1_1") (pintype "passive"))
      (node (ref "R10") (pin "2") (pinfunction "2_2") (pintype "passive"))
    )
    (net (code "51") (name "/Сеть 123") (class "Default")
      (node (ref "K1") (pin "5") (pinfunction "5_5") (pintype "passive"))
      (node (ref "R29") (pin "2") (pinfunction "2_2") (pintype "passive"))
    )
    (net (code "52") (name "/Сеть 124") (class "Default")
      (node (ref "C117") (pin "2") (pinfunction "2_2") (pintype "passive"))
      (node (ref "D22") (pin "1") (pinfunction "K_1") (pintype "passive"))
      (node (ref "R50") (pin "1") (pinfunction "1_1") (pintype "passive"))
    )
    (net (code "53") (name "/Сеть 125") (class "Default")
      (node (ref "C44") (pin "2") (pinfunction "2_2") (pintype "passive"))
      (node (ref "C52") (pin "2") (pinfunction "2_2") (pintype "passive"))
      (node (ref "L22") (pin "2") (pinfunction "2_2") (pintype "passive"))
    )
    (net (code "54") (name "/Сеть 128") (class "Default")
      (node (ref "C105") (pin "1") (pinfunction "1_1") (pintype "passive"))
      (node (ref "C95") (pin "1") (pinfunction "1_1") (pintype "passive"))
      (node (ref "L37") (pin "2") (pinfunction "B_2") (pintype "passive"))
      (node (ref "L38") (pin "1") (pinfunction "A_1") (pintype "passive"))
      (node (ref "L43") (pin "1") (pinfunction "A_1") (pintype "passive"))
      (node (ref "R47") (pin "2") (pinfunction "2_2") (pintype "passive"))
      (node (ref "R48") (pin "1") (pinfunction "1_1") (pintype "passive"))
    )
    (net (code "55") (name "/Сеть 129") (class "Default")
      (node (ref "C126") (pin "2") (pinfunction "2_2") (pintype "passive"))
      (node (ref "Q2") (pin "3") (pinfunction "D_3") (pintype "passive"))
      (node (ref "U5") (pin "3") (pinfunction "IN_3") (pintype "passive"))
    )
    (net (code "56") (name "/Сеть 131") (class "Default")
      (node (ref "C80") (pin "2") (pinfunction "2_2") (pintype "passive"))
      (node (ref "R37") (pin "1") (pinfunction "1_1") (pintype "passive"))
      (node (ref "T5") (pin "1") (pinfunction "S1_1") (pintype "passive"))
      (node (ref "T5") (pin "7") (pinfunction "7_7") (pintype "passive"))
    )
    (net (code "57") (name "/Сеть 132") (class "Default")
      (node (ref "C38") (pin "2") (pinfunction "2_2") (pintype "passive"))
      (node (ref "R33") (pin "1") (pinfunction "1_1") (pintype "passive"))
      (node (ref "T5") (pin "3") (pinfunction "S3_3") (pintype "passive"))
      (node (ref "T5") (pin "9") (pinfunction "9_9") (pintype "passive"))
    )
    (net (code "58") (name "/Сеть 133") (class "Default")
      (node (ref "C80") (pin "1") (pinfunction "1_1") (pintype "passive"))
      (node (ref "R37") (pin "2") (pinfunction "2_2") (pintype "passive"))
      (node (ref "R38") (pin "1") (pinfunction "1_1") (pintype "passive"))
      (node (ref "R43") (pin "1") (pinfunction "1_1") (pintype "passive"))
    )
    (net (code "59") (name "/Сеть 134") (class "Default")
      (node (ref "C38") (pin "1") (pinfunction "1_1") (pintype "passive"))
      (node (ref "R33") (pin "2") (pinfunction "2_2") (pintype "passive"))
      (node (ref "R34") (pin "1") (pinfunction "1_1") (pintype "passive"))
      (node (ref "R42") (pin "2") (pinfunction "2_2") (pintype "passive"))
    )
    (net (code "60") (name "/Сеть 135") (class "Default")
      (node (ref "C114") (pin "1") (pinfunction "1_1") (pintype "passive"))
      (node (ref "C116") (pin "1") (pinfunction "1_1") (pintype "passive"))
      (node (ref "R42") (pin "1") (pinfunction "1_1") (pintype "passive"))
      (node (ref "R43") (pin "2") (pinfunction "2_2") (pintype "passive"))
      (node (ref "R44") (pin "2") (pinfunction "2_2") (pintype "passive"))
      (node (ref "R51") (pin "1") (pinfunction "A_1") (pintype "passive"))
      (node (ref "T5") (pin "2") (pinfunction "S2_2") (pintype "passive"))
      (node (ref "T5") (pin "8") (pinfunction "8_8") (pintype "passive"))
    )
    (net (code "61") (name "/Сеть 136") (class "Default")
      (node (ref "C81") (pin "1") (pinfunction "1_1") (pintype "passive"))
      (node (ref "R46") (pin "2") (pinfunction "2_2") (pintype "passive"))
    )
    (net (code "62") (name "/Сеть 137") (class "Default")
      (node (ref "C81") (pin "2") (pinfunction "2_2") (pintype "passive"))
      (node (ref "C93") (pin "1") (pinfunction "1_1") (pintype "passive"))
      (node (ref "C94") (pin "1") (pinfunction "1_1") (pintype "passive"))
      (node (ref "L38") (pin "2") (pinfunction "B_2") (pintype "passive"))
      (node (ref "Q3") (pin "1") (pinfunction "D_1") (pintype "passive"))
      (node (ref "R47") (pin "1") (pinfunction "1_1") (pintype "passive"))
    )
    (net (code "63") (name "/Сеть 139") (class "Default")
      (node (ref "C91") (pin "2") (pinfunction "2_2") (pintype "passive"))
      (node (ref "C92") (pin "2") (pinfunction "2_2") (pintype "passive"))
      (node (ref "T4") (pin "1") (pinfunction "P1_1") (pintype "passive"))
    )
    (net (code "64") (name "/Сеть 140") (class "Default")
      (node (ref "R52") (pin "2") (pinfunction "2_2") (pintype "passive"))
      (node (ref "R53") (pin "2") (pinfunction "2_2") (pintype "passive"))
      (node (ref "U5") (pin "1") (pinfunction "ADJ/GND_1") (pintype "passive"))
    )
    (net (code "65") (name "/Сеть 150") (class "Default")
      (node (ref "U7") (pin "15") (pinfunction "QA_15") (pintype "tri_state"))
      (node (ref "U8") (pin "1") (pinfunction "1B_1") (pintype "passive"))
    )
    (net (code "66") (name "/Сеть 154") (class "Default")
      (node (ref "U7") (pin "4") (pinfunction "QE_4") (pintype "tri_state"))
      (node (ref "U8") (pin "5") (pinfunction "5B_5") (pintype "passive"))
    )
    (net (code "67") (name "/Сеть 155") (class "Default")
      (node (ref "U7") (pin "5") (pinfunction "QF_5") (pintype "tri_state"))
      (node (ref "U8") (pin "6") (pinfunction "6B_6") (pintype "passive"))
    )
    (net (code "68") (name "/Сеть 156") (class "Default")
      (node (ref "U7") (pin "6") (pinfunction "QG_6") (pintype "tri_state"))
      (node (ref "U8") (pin "7") (pinfunction "7B_7") (pintype "passive"))
    )
    (net (code "69") (name "/Сеть 166") (class "Default")
      (node (ref "C13") (pin "2") (pinfunction "2_2") (pintype "passive"))
      (node (ref "D4") (pin "1") (pinfunction "(C)_1") (pintype "passive"))
      (node (ref "L4") (pin "2") (pinfunction "2_2") (pintype "passive"))
      (node (ref "L7") (pin "1") (pinfunction "1_1") (pintype "passive"))
    )
    (net (code "70") (name "/Сеть 185") (class "Default")
      (node (ref "C44") (pin "1") (pinfunction "1_1") (pintype "passive"))
      (node (ref "C47") (pin "2") (pinfunction "2_2") (pintype "passive"))
      (node (ref "C50") (pin "2") (pinfunction "2_2") (pintype "passive"))
      (node (ref "C52") (pin "1") (pinfunction "1_1") (pintype "passive"))
      (node (ref "L20") (pin "2") (pinfunction "2_2") (pintype "passive"))
      (node (ref "L23") (pin "1") (pinfunction "1_1") (pintype "passive"))
    )
    (net (code "71") (name "/Сеть 195") (class "Default")
      (node (ref "C45") (pin "1") (pinfunction "1_1") (pintype "passive"))
      (node (ref "C48") (pin "2") (pinfunction "2_2") (pintype "passive"))
      (node (ref "C51") (pin "2") (pinfunction "2_2") (pintype "passive"))
      (node (ref "C53") (pin "1") (pinfunction "1_1") (pintype "passive"))
      (node (ref "D11") (pin "1") (pinfunction "(C)_1") (pintype "passive"))
      (node (ref "L21") (pin "2") (pinfunction "2_2") (pintype "passive"))
    )
    (net (code "72") (name "/Сеть 196") (class "Default")
      (node (ref "C45") (pin "2") (pinfunction "2_2") (pintype "passive"))
      (node (ref "C53") (pin "2") (pinfunction "2_2") (pintype "passive"))
      (node (ref "L23") (pin "2") (pinfunction "2_2") (pintype "passive"))
    )
    (net (code "73") (name "/Сеть 199") (class "Default")
      (node (ref "C54") (pin "2") (pinfunction "2_2") (pintype "passive"))
      (node (ref "C55") (pin "2") (pinfunction "2_2") (pintype "passive"))
      (node (ref "L24") (pin "1") (pinfunction "1_1") (pintype "passive"))
      (node (ref "R11") (pin "2") (pinfunction "2_2") (pintype "passive"))
      (node (ref "R12") (pin "1") (pinfunction "1_1") (pintype "passive"))
    )
    (net (code "74") (name "/Сеть 200") (class "Default")
      (node (ref "C56") (pin "2") (pinfunction "2_2") (pintype "passive"))
      (node (ref "C57") (pin "2") (pinfunction "2_2") (pintype "passive"))
      (node (ref "C62") (pin "1") (pinfunction "1_1") (pintype "passive"))
      (node (ref "C65") (pin "1") (pinfunction "1_1") (pintype "passive"))
      (node (ref "L26") (pin "1") (pinfunction "1_1") (pintype "passive"))
      (node (ref "R12") (pin "2") (pinfunction "2_2") (pintype "passive"))
    )
    (net (code "75") (name "/Сеть 201") (class "Default")
      (node (ref "C58") (pin "2") (pinfunction "2_2") (pintype "passive"))
      (node (ref "C66") (pin "2") (pinfunction "2_2") (pintype "passive"))
      (node (ref "L27") (pin "2") (pinfunction "2_2") (pintype "passive"))
    )
    (net (code "76") (name "/Сеть 202") (class "Default")
      (node (ref "C58") (pin "1") (pinfunction "1_1") (pintype "passive"))
      (node (ref "C61") (pin "2") (pinfunction "2_2") (pintype "passive"))
      (node (ref "C64") (pin "2") (pinfunction "2_2") (pintype "passive"))
      (node (ref "C66") (pin "1") (pinfunction "1_1") (pintype "passive"))
      (node (ref "L25") (pin "2") (pinfunction "2_2") (pintype "passive"))
      (node (ref "L28") (pin "1") (pinfunction "1_1") (pintype "passive"))
    )
    (net (code "77") (name "/Сеть 203") (class "Default")
      (node (ref "C59") (pin "1") (pinfunction "1_1") (pintype "passive"))
      (node (ref "C62") (pin "2") (pinfunction "2_2") (pintype "passive"))
      (node (ref "C65") (pin "2") (pinfunction "2_2") (pintype "passive"))
      (node (ref "C67") (pin "1") (pinfunction "1_1") (pintype "passive"))
      (node (ref "D13") (pin "1") (pinfunction "(C)_1") (pintype "passive"))
      (node (ref "L26") (pin "2") (pinfunction "2_2") (pintype "passive"))
    )
    (net (code "78") (name "/Сеть 204") (class "Default")
      (node (ref "C59") (pin "2") (pinfunction "2_2") (pintype "passive"))
      (node (ref "C67") (pin "2") (pinfunction "2_2") (pintype "passive"))
      (node (ref "L28") (pin "2") (pinfunction "2_2") (pintype "passive"))
    )
    (net (code "79") (name "/Сеть 207") (class "Default")
      (node (ref "C68") (pin "2") (pinfunction "2_2") (pintype "passive"))
      (node (ref "C69") (pin "2") (pinfunction "2_2") (pintype "passive"))
      (node (ref "L29") (pin "1") (pinfunction "1_1") (pintype "passive"))
      (node (ref "R13") (pin "2") (pinfunction "2_2") (pintype "passive"))
      (node (ref "R14") (pin "1") (pinfunction "1_1") (pintype "passive"))
    )
    (net (code "80") (name "/Сеть 208") (class "Default")
      (node (ref "C70") (pin "2") (pinfunction "2_2") (pintype "passive"))
      (node (ref "C71") (pin "2") (pinfunction "2_2") (pintype "passive"))
      (node (ref "C76") (pin "1") (pinfunction "1_1") (pintype "passive"))
      (node (ref "C79") (pin "1") (pinfunction "1_1") (pintype "passive"))
      (node (ref "L31") (pin "1") (pinfunction "1_1") (pintype "passive"))
      (node (ref "R14") (pin "2") (pinfunction "2_2") (pintype "passive"))
    )
    (net (code "81") (name "/Сеть 209") (class "Default")
      (node (ref "C72") (pin "2") (pinfunction "2_2") (pintype "passive"))
      (node (ref "L32") (pin "2") (pinfunction "2_2") (pintype "passive"))
    )
    (net (code "82") (name "/Сеть 210") (class "Default")
      (node (ref "C72") (pin "1") (pinfunction "1_1") (pintype "passive"))
      (node (ref "C75") (pin "2") (pinfunction "2_2") (pintype "passive"))
      (node (ref "C78") (pin "2") (pinfunction "2_2") (pintype "passive"))
      (node (ref "L30") (pin "2") (pinfunction "2_2") (pintype "passive"))
      (node (ref "L33") (pin "1") (pinfunction "1_1") (pintype "passive"))
    )
    (net (code "83") (name "/Сеть 211") (class "Default")
      (node (ref "C73") (pin "1") (pinfunction "1_1") (pintype "passive"))
      (node (ref "C76") (pin "2") (pinfunction "2_2") (pintype "passive"))
      (node (ref "C79") (pin "2") (pinfunction "2_2") (pintype "passive"))
      (node (ref "D15") (pin "1") (pinfunction "(C)_1") (pintype "passive"))
      (node (ref "L31") (pin "2") (pinfunction "2_2") (pintype "passive"))
    )
    (net (code "84") (name "/Сеть 212") (class "Default")
      (node (ref "C73") (pin "2") (pinfunction "2_2") (pintype "passive"))
      (node (ref "L33") (pin "2") (pinfunction "2_2") (pintype "passive"))
    )
    (net (code "85") (name "/Сеть 213") (class "Default")
      (node (ref "D11") (pin "2") (pinfunction "(A)_2") (pintype "passive"))
      (node (ref "D13") (pin "2") (pinfunction "(A)_2") (pintype "passive"))
      (node (ref "D15") (pin "2") (pinfunction "(A)_2") (pintype "passive"))
      (node (ref "D17") (pin "2") (pinfunction "(A)_2") (pintype "passive"))
      (node (ref "D2") (pin "2") (pinfunction "(A)_2") (pintype "passive"))
      (node (ref "D5") (pin "2") (pinfunction "(A)_2") (pintype "passive"))
      (node (ref "D7") (pin "2") (pinfunction "(A)_2") (pintype "passive"))
      (node (ref "D9") (pin "2") (pinfunction "(A)_2") (pintype "passive"))
      (node (ref "T2") (pin "1") (pinfunction "P1_1") (pintype "passive"))
      (node (ref "T2") (pin "7") (pinfunction "0_7") (pintype "passive"))
    )
    (net (code "86") (name "/Сеть 214") (class "Default")
      (node (ref "C86") (pin "2") (pinfunction "2_2") (pintype "passive"))
      (node (ref "C88") (pin "2") (pinfunction "2_2") (pintype "passive"))
      (node (ref "D16") (pin "1") (pinfunction "(C)_1") (pintype "passive"))
      (node (ref "L34") (pin "2") (pinfunction "2_2") (pintype "passive"))
    )
    (net (code "87") (name "/Сеть 215") (class "Default")
      (node (ref "C82") (pin "2") (pinfunction "2_2") (pintype "passive"))
      (node (ref "C83") (pin "2") (pinfunction "2_2") (pintype "passive"))
      (node (ref "L34") (pin "1") (pinfunction "1_1") (pintype "passive"))
      (node (ref "R15") (pin "2") (pinfunction "2_2") (pintype "passive"))
      (node (ref "R16") (pin "1") (pinfunction "1_1") (pintype "passive"))
    )
    (net (code "88") (name "/Сеть 216") (class "Default")
      (node (ref "C84") (pin "2") (pinfunction "2_2") (pintype "passive"))
      (node (ref "C85") (pin "2") (pinfunction "2_2") (pintype "passive"))
      (node (ref "C90") (pin "1") (pinfunction "1_1") (pintype "passive"))
      (node (ref "L36") (pin "1") (pinfunction "1_1") (pintype "passive"))
      (node (ref "R16") (pin "2") (pinfunction "2_2") (pintype "passive"))
    )
    (net (code "89") (name "/Сеть 218") (class "Default")
      (node (ref "C86") (pin "1") (pinfunction "1_1") (pintype "passive"))
      (node (ref "C87") (pin "2") (pinfunction "2_2") (pintype "passive"))
      (node (ref "C89") (pin "2") (pinfunction "2_2") (pintype "passive"))
      (node (ref "L35") (pin "2") (pinfunction "2_2") (pintype "passive"))
    )
    (net (code "90") (name "/Сеть 219") (class "Default")
      (node (ref "C87") (pin "1") (pinfunction "1_1") (pintype "passive"))
      (node (ref "C90") (pin "2") (pinfunction "2_2") (pintype "passive"))
      (node (ref "D17") (pin "1") (pinfunction "(C)_1") (pintype "passive"))
      (node (ref "L36") (pin "2") (pinfunction "2_2") (pintype "passive"))
    )
    (net (code "91") (name "/Сеть 222") (class "Default")
      (node (ref "D1") (pin "2") (pinfunction "(A)_2") (pintype "passive"))
      (node (ref "D10") (pin "2") (pinfunction "(A)_2") (pintype "passive"))
      (node (ref "D12") (pin "2") (pinfunction "(A)_2") (pintype "passive"))
      (node (ref "D14") (pin "2") (pinfunction "(A)_2") (pintype "passive"))
      (node (ref "D16") (pin "2") (pinfunction "(A)_2") (pintype "passive"))
      (node (ref "D4") (pin "2") (pinfunction "(A)_2") (pintype "passive"))
      (node (ref "D6") (pin "2") (pinfunction "(A)_2") (pintype "passive"))
      (node (ref "D8") (pin "2") (pinfunction "(A)_2") (pintype "passive"))
      (node (ref "T1") (pin "3") (pinfunction "S1_3") (pintype "passive"))
      (node (ref "T1") (pin "9") (pinfunction "0_9") (pintype "passive"))
    )
    (net (code "92") (name "/Сеть 223") (class "Default")
      (node (ref "C96") (pin "2") (pinfunction "2_2") (pintype "passive"))
      (node (ref "C97") (pin "2") (pinfunction "2_2") (pintype "passive"))
      (node (ref "R17") (pin "1") (pinfunction "1_1") (pintype "passive"))
      (node (ref "T1") (pin "1") (pinfunction "S3_1") (pintype "passive"))
      (node (ref "T1") (pin "7") (pinfunction "0_7") (pintype "passive"))
    )
    (net (code "93") (name "/Сеть 224") (class "Default")
      (node (ref "C98") (pin "2") (pinfunction "2_2") (pintype "passive"))
      (node (ref "C99") (pin "2") (pinfunction "2_2") (pintype "passive"))
      (node (ref "R18") (pin "2") (pinfunction "2_2") (pintype "passive"))
      (node (ref "T2") (pin "3") (pinfunction "P2_3") (pintype "passive"))
      (node (ref "T2") (pin "9") (pinfunction "0_9") (pintype "passive"))
    )
    (net (code "94") (name "/Сеть 227") (class "Default")
      (node (ref "R27") (pin "2") (pinfunction "2_2") (pintype "passive"))
      (node (ref "R28") (pin "1") (pinfunction "1_1") (pintype "passive"))
      (node (ref "R30") (pin "2") (pinfunction "2_2") (pintype "passive"))
    )
    (net (code "95") (name "/Сеть 228") (class "Default")
      (node (ref "R28") (pin "2") (pinfunction "2_2") (pintype "passive"))
      (node (ref "R29") (pin "1") (pinfunction "1_1") (pintype "passive"))
      (node (ref "R31") (pin "2") (pinfunction "2_2") (pintype "passive"))
    )
    (net (code "96") (name "/Сеть 234") (class "Default")
      (node (ref "C101") (pin "1") (pinfunction "1_1") (pintype "passive"))
      (node (ref "C102") (pin "2") (pinfunction "2_2") (pintype "passive"))
      (node (ref "C106") (pin "2") (pinfunction "2_2") (pintype "passive"))
      (node (ref "C107") (pin "2") (pinfunction "2_2") (pintype "passive"))
      (node (ref "L40") (pin "2") (pinfunction "2_2") (pintype "passive"))
      (node (ref "L41") (pin "1") (pinfunction "1_1") (pintype "passive"))
    )
    (net (code "97") (name "/Сеть 236") (class "Default")
      (node (ref "C102") (pin "1") (pinfunction "1_1") (pintype "passive"))
      (node (ref "C103") (pin "2") (pinfunction "2_2") (pintype "passive"))
      (node (ref "C108") (pin "2") (pinfunction "2_2") (pintype "passive"))
      (node (ref "C109") (pin "2") (pinfunction "2_2") (pintype "passive"))
      (node (ref "L41") (pin "2") (pinfunction "2_2") (pintype "passive"))
      (node (ref "L42") (pin "1") (pinfunction "1_1") (pintype "passive"))
    )
    (net (code "98") (name "/Сеть 243") (class "Default")
      (node (ref "U1") (pin "15") (pinfunction "QA_15") (pintype "tri_state"))
      (node (ref "U2") (pin "1") (pinfunction "1B_1") (pintype "passive"))
    )
    (net (code "99") (name "/Сеть 244") (class "Default")
      (node (ref "U1") (pin "1") (pinfunction "QB_1") (pintype "tri_state"))
      (node (ref "U2") (pin "2") (pinfunction "2B_2") (pintype "passive"))
    )
    (net (code "100") (name "/Сеть 245") (class "Default")
      (node (ref "U1") (pin "2") (pinfunction "QC_2") (pintype "tri_state"))
      (node (ref "U2") (pin "3") (pinfunction "3B_3") (pintype "passive"))
    )
    (net (code "101") (name "/Сеть 246") (class "Default")
      (node (ref "U1") (pin "3") (pinfunction "QD_3") (pintype "tri_state"))
      (node (ref "U2") (pin "4") (pinfunction "4B_4") (pintype "passive"))
    )
    (net (code "102") (name "/Сеть 247") (class "Default")
      (node (ref "U1") (pin "4") (pinfunction "QE_4") (pintype "tri_state"))
      (node (ref "U2") (pin "5") (pinfunction "5B_5") (pintype "passive"))
    )
    (net (code "103") (name "/Сеть 248") (class "Default")
      (node (ref "U1") (pin "5") (pinfunction "QF_5") (pintype "tri_state"))
      (node (ref "U2") (pin "6") (pinfunction "6B_6") (pintype "passive"))
    )
    (net (code "104") (name "/Сеть 249") (class "Default")
      (node (ref "U1") (pin "6") (pinfunction "QG_6") (pintype "tri_state"))
      (node (ref "U2") (pin "7") (pinfunction "7B_7") (pintype "passive"))
    )
    (net (code "105") (name "AMP_OUT") (class "Default")
      (node (ref "C123") (pin "2") (pinfunction "2_2") (pintype "passive"))
      (node (ref "L44") (pin "1") (pinfunction "A_1") (pintype "passive"))
      (node (ref "T4") (pin "2") (pinfunction "P2_2") (pintype "passive"))
    )
    (net (code "106") (name "ATT_ON") (class "Default")
      (node (ref "D18") (pin "2") (pinfunction "A_2") (pintype "passive"))
      (node (ref "K1") (pin "8") (pinfunction "8_8") (pintype "passive"))
      (node (ref "U2") (pin "10") (pinfunction "7C_10") (pintype "passive"))
    )
    (net (code "107") (name "BPF_OFF") (class "Default")
      (node (ref "D20") (pin "2") (pinfunction "A_2") (pintype "passive"))
      (node (ref "K4") (pin "8") (pinfunction "8_8") (pintype "passive"))
      (node (ref "U2") (pin "12") (pinfunction "5C_12") (pintype "passive"))
    )
    (net (code "108") (name "BPF_ON_0") (class "Default")
      (node (ref "R15") (pin "1") (pinfunction "1_1") (pintype "passive"))
      (node (ref "R19") (pin "2") (pinfunction "2_2") (pintype "passive"))
      (node (ref "U2") (pin "13") (pinfunction "4C_13") (pintype "passive"))
    )
    (net (code "109") (name "BPF_ON_1") (class "Default")
      (node (ref "R13") (pin "1") (pinfunction "1_1") (pintype "passive"))
      (node (ref "R20") (pin "2") (pinfunction "2_2") (pintype "passive"))
      (node (ref "U4") (pin "14") (pinfunction "3C_14") (pintype "passive"))
    )
    (net (code "110") (name "BPF_ON_2") (class "Default")
      (node (ref "R11") (pin "1") (pinfunction "1_1") (pintype "passive"))
      (node (ref "R21") (pin "2") (pinfunction "2_2") (pintype "passive"))
      (node (ref "U4") (pin "13") (pinfunction "4C_13") (pintype "passive"))
    )
    (net (code "111") (name "BPF_ON_3") (class "Default")
      (node (ref "R22") (pin "2") (pinfunction "2_2") (pintype "passive"))
      (node (ref "R9") (pin "1") (pinfunction "1_1") (pintype "passive"))
      (node (ref "U4") (pin "12") (pinfunction "5C_12") (pintype "passive"))
    )
    (net (code "112") (name "BPF_ON_4") (class "Default")
      (node (ref "R23") (pin "2") (pinfunction "2_2") (pintype "passive"))
      (node (ref "R7") (pin "1") (pinfunction "1_1") (pintype "passive"))
      (node (ref "U4") (pin "11") (pinfunction "6C_11") (pintype "passive"))
    )
    (net (code "113") (name "BPF_ON_5") (class "Default")
      (node (ref "R24") (pin "2") (pinfunction "2_2") (pintype "passive"))
      (node (ref "R5") (pin "1") (pinfunction "1_1") (pintype "passive"))
      (node (ref "U4") (pin "10") (pinfunction "7C_10") (pintype "passive"))
    )
    (net (code "114") (name "BPF_ON_6") (class "Default")
      (node (ref "R25") (pin "2") (pinfunction "2_2") (pintype "passive"))
      (node (ref "R3") (pin "1") (pinfunction "1_1") (pintype "passive"))
      (node (ref "U2") (pin "15") (pinfunction "2C_15") (pintype "passive"))
    )
    (net (code "115") (name "BPF_ON_7") (class "Default")
      (node (ref "R1") (pin "1") (pinfunction "1_1") (pintype "passive"))
      (node (ref "R26") (pin "2") (pinfunction "2_2") (pintype "passive"))
      (node (ref "U2") (pin "14") (pinfunction "3C_14") (pintype "passive"))
    )
    (net (code "116") (name "BPF_VCC") (class "Default")
      (node (ref "C100") (pin "2") (pinfunction "2_2") (pintype "passive"))
      (node (ref "L39") (pin "1") (pinfunction "1_1") (pintype "passive"))
      (node (ref "R17") (pin "2") (pinfunction "2_2") (pintype "passive"))
      (node (ref "R18") (pin "1") (pinfunction "1_1") (pintype "passive"))
      (node (ref "R19") (pin "1") (pinfunction "1_1") (pintype "passive"))
      (node (ref "R20") (pin "1") (pinfunction "1_1") (pintype "passive"))
      (node (ref "R21") (pin "1") (pinfunction "1_1") (pintype "passive"))
      (node (ref "R22") (pin "1") (pinfunction "1_1") (pintype "passive"))
      (node (ref "R23") (pin "1") (pinfunction "1_1") (pintype "passive"))
      (node (ref "R24") (pin "1") (pinfunction "1_1") (pintype "passive"))
      (node (ref "R25") (pin "1") (pinfunction "1_1") (pintype "passive"))
      (node (ref "R26") (pin "1") (pinfunction "1_1") (pintype "passive"))
    )
    (net (code "117") (name "CTRL_CLK") (class "Default")
      (node (ref "J4") (pin "4") (pinfunction "CLK_4") (pintype "output"))
      (node (ref "U1") (pin "11") (pinfunction "SRCLK_11") (pintype "input"))
      (node (ref "U3") (pin "11") (pinfunction "SRCLK_11") (pintype "input"))
      (node (ref "U7") (pin "11") (pinfunction "SRCLK_11") (pintype "input"))
    )
    (net (code "118") (name "CTRL_DATA") (class "Default")
      (node (ref "J4") (pin "6") (pinfunction "DATA_6") (pintype "output"))
      (node (ref "U3") (pin "14") (pinfunction "SER_14") (pintype "input"))
    )
    (net (code "119") (name "CTRL_OE") (class "Default")
      (node (ref "J4") (pin "5") (pinfunction "OE_5") (pintype "output"))
      (node (ref "R35") (pin "2") (pinfunction "2_2") (pintype "passive"))
      (node (ref "U1") (pin "13") (pinfunction "~{OE}_13") (pintype "input"))
      (node (ref "U3") (pin "13") (pinfunction "~{OE}_13") (pintype "input"))
      (node (ref "U7") (pin "13") (pinfunction "~{OE}_13") (pintype "input"))
    )
    (net (code "120") (name "CTRL_RCLK") (class "Default")
      (node (ref "J4") (pin "3") (pinfunction "RCLK_3") (pintype "output"))
      (node (ref "U1") (pin "12") (pinfunction "RCLK_12") (pintype "input"))
      (node (ref "U3") (pin "12") (pinfunction "RCLK_12") (pintype "input"))
      (node (ref "U7") (pin "12") (pinfunction "RCLK_12") (pintype "input"))
    )
    (net (code "121") (name "GND") (class "Default")
      (node (ref "C1") (pin "1") (pinfunction "1_1") (pintype "passive"))
      (node (ref "C10") (pin "1") (pinfunction "1_1") (pintype "passive"))
      (node (ref "C100") (pin "1") (pinfunction "1_1") (pintype "passive"))
      (node (ref "C104") (pin "1") (pinfunction "1_1") (pintype "passive"))
      (node (ref "C105") (pin "2") (pinfunction "2_2") (pintype "passive"))
      (node (ref "C106") (pin "1") (pinfunction "1_1") (pintype "passive"))
      (node (ref "C107") (pin "1") (pinfunction "1_1") (pintype "passive"))
      (node (ref "C108") (pin "1") (pinfunction "1_1") (pintype "passive"))
      (node (ref "C109") (pin "1") (pinfunction "1_1") (pintype "passive"))
      (node (ref "C110") (pin "1") (pinfunction "1_1") (pintype "passive"))
      (node (ref "C113") (pin "2") (pinfunction "2_2") (pintype "passive"))
      (node (ref "C114") (pin "2") (pinfunction "2_2") (pintype "passive"))
      (node (ref "C115") (pin "1") (pinfunction "1_1") (pintype "passive"))
      (node (ref "C116") (pin "2") (pinfunction "2_2") (pintype "passive"))
      (node (ref "C117") (pin "1") (pinfunction "1_1") (pintype "passive"))
      (node (ref "C118") (pin "1") (pinfunction "1_1") (pintype "passive"))
      (node (ref "C119") (pin "2") (pinfunction "MINUS_2") (pintype "passive"))
      (node (ref "C121") (pin "1") (pinfunction "1_1") (pintype "passive"))
      (node (ref "C122") (pin "1") (pinfunction "1_1") (pintype "passive"))
      (node (ref "C123") (pin "1") (pinfunction "1_1") (pintype "passive"))
      (node (ref "C124") (pin "1") (pinfunction "1_1") (pintype "passive"))
      (node (ref "C125") (pin "1") (pinfunction "1_1") (pintype "passive"))
      (node (ref "C126") (pin "1") (pinfunction "1_1") (pintype "passive"))
      (node (ref "C127") (pin "1") (pinfunction "1_1") (pintype "passive"))
      (node (ref "C128") (pin "2") (pinfunction "2_2") (pintype "passive"))
      (node (ref "C129") (pin "2") (pinfunction "MINUS_2") (pintype "passive"))
      (node (ref "C13") (pin "1") (pinfunction "1_1") (pintype "passive"))
      (node (ref "C130") (pin "1") (pinfunction "1_1") (pintype "passive"))
      (node (ref "C133") (pin "1") (pinfunction "1_1") (pintype "passive"))
      (node (ref "C14") (pin "1") (pinfunction "1_1") (pintype "passive"))
      (node (ref "C16") (pin "1") (pinfunction "1_1") (pintype "passive"))
      (node (ref "C17") (pin "1") (pinfunction "1_1") (pintype "passive"))
      (node (ref "C18") (pin "1") (pinfunction "1_1") (pintype "passive"))
      (node (ref "C19") (pin "1") (pinfunction "1_1") (pintype "passive"))
      (node (ref "C2") (pin "1") (pinfunction "1_1") (pintype "passive"))
      (node (ref "C22") (pin "1") (pinfunction "1_1") (pintype "passive"))
      (node (ref "C23") (pin "1") (pinfunction "1_1") (pintype "passive"))
      (node (ref "C25") (pin "1") (pinfunction "1_1") (pintype "passive"))
      (node (ref "C26") (pin "1") (pinfunction "1_1") (pintype "passive"))
      (node (ref "C28") (pin "1") (pinfunction "1_1") (pintype "passive"))
      (node (ref "C29") (pin "1") (pinfunction "1_1") (pintype "passive"))
      (node (ref "C3") (pin "1") (pinfunction "1_1") (pintype "passive"))
      (node (ref "C30") (pin "1") (pinfunction "1_1") (pintype "passive"))
      (node (ref "C31") (pin "1") (pinfunction "1_1") (pintype "passive"))
      (node (ref "C34") (pin "1") (pinfunction "1_1") (pintype "passive"))
      (node (ref "C35") (pin "1") (pinfunction "1_1") (pintype "passive"))
      (node (ref "C37") (pin "1") (pinfunction "1_1") (pintype "passive"))
      (node (ref "C4") (pin "1") (pinfunction "1_1") (pintype "passive"))
      (node (ref "C40") (pin "1") (pinfunction "1_1") (pintype "passive"))
      (node (ref "C41") (pin "1") (pinfunction "1_1") (pintype "passive"))
      (node (ref "C42") (pin "1") (pinfunction "1_1") (pintype "passive"))
      (node (ref "C43") (pin "1") (pinfunction "1_1") (pintype "passive"))
      (node (ref "C46") (pin "1") (pinfunction "1_1") (pintype "passive"))
      (node (ref "C47") (pin "1") (pinfunction "1_1") (pintype "passive"))
      (node (ref "C49") (pin "1") (pinfunction "1_1") (pintype "passive"))
      (node (ref "C50") (pin "1") (pinfunction "1_1") (pintype "passive"))
      (node (ref "C54") (pin "1") (pinfunction "1_1") (pintype "passive"))
      (node (ref "C55") (pin "1") (pinfunction "1_1") (pintype "passive"))
      (node (ref "C56") (pin "1") (pinfunction "1_1") (pintype "passive"))
      (node (ref "C57") (pin "1") (pinfunction "1_1") (pintype "passive"))
      (node (ref "C60") (pin "1") (pinfunction "1_1") (pintype "passive"))
      (node (ref "C61") (pin "1") (pinfunction "1_1") (pintype "passive"))
      (node (ref "C63") (pin "1") (pinfunction "1_1") (pintype "passive"))
      (node (ref "C64") (pin "1") (pinfunction "1_1") (pintype "passive"))
      (node (ref "C68") (pin "1") (pinfunction "1_1") (pintype "passive"))
      (node (ref "C69") (pin "1") (pinfunction "1_1") (pintype "passive"))
      (node (ref "C7") (pin "1") (pinfunction "1_1") (pintype "passive"))
      (node (ref "C70") (pin "1") (pinfunction "1_1") (pintype "passive"))
      (node (ref "C71") (pin "1") (pinfunction "1_1") (pintype "passive"))
      (node (ref "C74") (pin "1") (pinfunction "1_1") (pintype "passive"))
      (node (ref "C75") (pin "1") (pinfunction "1_1") (pintype "passive"))
      (node (ref "C77") (pin "1") (pinfunction "1_1") (pintype "passive"))
      (node (ref "C78") (pin "1") (pinfunction "1_1") (pintype "passive"))
      (node (ref "C8") (pin "1") (pinfunction "1_1") (pintype "passive"))
      (node (ref "C82") (pin "1") (pinfunction "1_1") (pintype "passive"))
      (node (ref "C83") (pin "1") (pinfunction "1_1") (pintype "passive"))
      (node (ref "C84") (pin "1") (pinfunction "1_1") (pintype "passive"))
      (node (ref "C85") (pin "1") (pinfunction "1_1") (pintype "passive"))
      (node (ref "C88") (pin "1") (pinfunction "1_1") (pintype "passive"))
      (node (ref "C89") (pin "1") (pinfunction "1_1") (pintype "passive"))
      (node (ref "C9") (pin "1") (pinfunction "1_1") (pintype "passive"))
      (node (ref "C95") (pin "2") (pinfunction "2_2") (pintype "passive"))
      (node (ref "C96") (pin "1") (pinfunction "1_1") (pintype "passive"))
      (node (ref "C97") (pin "1") (pinfunction "1_1") (pintype "passive"))
      (node (ref "C98") (pin "1") (pinfunction "1_1") (pintype "passive"))
      (node (ref "C99") (pin "1") (pinfunction "1_1") (pintype "passive"))
      (node (ref "D24") (pin "1") (pinfunction "A(D1)_1") (pintype "passive"))
      (node (ref "D24") (pin "2") (pinfunction "C(D2)_2") (pintype "passive"))
      (node (ref "J1") (pin "1") (pinfunction "GND_1") (pintype "passive"))
      (node (ref "J1") (pin "2") (pinfunction "GND_2") (pintype "passive"))
      (node (ref "J1") (pin "3") (pinfunction "GND_3") (pintype "passive"))
      (node (ref "J1") (pin "4") (pinfunction "GND_4") (pintype "passive"))
      (node (ref "J2") (pin "1") (pinfunction "P1_1") (pintype "passive"))
      (node (ref "J4") (pin "2") (pinfunction "GND_2") (pintype "passive"))
      (node (ref "J8") (pin "1") (pinfunction "-_1") (pintype "passive"))
      (node (ref "J9") (pin "1") (pinfunction "P1_1") (pintype "passive"))
      (node (ref "L10") (pin "1") (pinfunction "1_1") (pintype "passive"))
      (node (ref "L15") (pin "1") (pinfunction "1_1") (pintype "passive"))
      (node (ref "L2") (pin "1") (pinfunction "1_1") (pintype "passive"))
      (node (ref "L20") (pin "1") (pinfunction "1_1") (pintype "passive"))
      (node (ref "L25") (pin "1") (pinfunction "1_1") (pintype "passive"))
      (node (ref "L30") (pin "1") (pinfunction "1_1") (pintype "passive"))
      (node (ref "L35") (pin "1") (pinfunction "1_1") (pintype "passive"))
      (node (ref "L5") (pin "1") (pinfunction "1_1") (pintype "passive"))
      (node (ref "Q1") (pin "2") (pinfunction "S_2") (pintype "passive"))
      (node (ref "Q3") (pin "2") (pinfunction "S_2") (pintype "passive"))
      (node (ref "Q4") (pin "0") (pinfunction "0_0") (pintype "passive"))
      (node (ref "Q4") (pin "2") (pinfunction "S_2") (pintype "passive"))
      (node (ref "R30") (pin "1") (pinfunction "1_1") (pintype "passive"))
      (node (ref "R31") (pin "1") (pinfunction "1_1") (pintype "passive"))
      (node (ref "R36") (pin "2") (pinfunction "2_2") (pintype "passive"))
      (node (ref "R40") (pin "1") (pinfunction "CCW_1") (pintype "passive"))
      (node (ref "R45") (pin "1") (pinfunction "1_1") (pintype "passive"))
      (node (ref "R51") (pin "2") (pinfunction "B_2") (pintype "passive"))
      (node (ref "R53") (pin "1") (pinfunction "1_1") (pintype "passive"))
      (node (ref "R54") (pin "1") (pinfunction "1_1") (pintype "passive"))
      (node (ref "R55") (pin "2") (pinfunction "2_2") (pintype "passive"))
      (node (ref "R56") (pin "2") (pinfunction "2_2") (pintype "passive"))
      (node (ref "T1") (pin "11") (pinfunction "0_11") (pintype "passive"))
      (node (ref "T1") (pin "4") (pinfunction "P1_4") (pintype "passive"))
      (node (ref "T2") (pin "10") (pinfunction "0_10") (pintype "passive"))
      (node (ref "T2") (pin "6") (pinfunction "S1_6") (pintype "passive"))
      (node (ref "T4") (pin "4") (pinfunction "S2_4") (pintype "passive"))
      (node (ref "T5") (pin "10") (pinfunction "10_10") (pintype "passive"))
      (node (ref "T5") (pin "6") (pinfunction "P1_6") (pintype "passive"))
      (node (ref "TSWR") (pin "7") (pinfunction "7_7") (pintype "passive"))
      (node (ref "U1") (pin "8") (pinfunction "GND_8") (pintype "power_in"))
      (node (ref "U2") (pin "8") (pinfunction "E_8") (pintype "passive"))
      (node (ref "U3") (pin "8") (pinfunction "GND_8") (pintype "power_in"))
      (node (ref "U4") (pin "8") (pinfunction "E_8") (pintype "passive"))
      (node (ref "U6") (pin "1") (pinfunction "ADJ/GND_1") (pintype "passive"))
      (node (ref "U7") (pin "8") (pinfunction "GND_8") (pintype "power_in"))
      (node (ref "U8") (pin "8") (pinfunction "E_8") (pintype "passive"))
    )
    (net (code "122") (name "LNA_RELAY") (class "Default")
      (node (ref "D26") (pin "2") (pinfunction "A_2") (pintype "passive"))
      (node (ref "K3") (pin "8") (pinfunction "8_8") (pintype "passive"))
      (node (ref "U8") (pin "10") (pinfunction "7C_10") (pintype "passive"))
    )
    (net (code "123") (name "LPF_OFF") (class "Default")
      (node (ref "D21") (pin "2") (pinfunction "A_2") (pintype "passive"))
      (node (ref "K5") (pin "8") (pinfunction "8_8") (pintype "passive"))
      (node (ref "U2") (pin "11") (pinfunction "6C_11") (pintype "passive"))
    )
    (net (code "124") (name "Net-(C101-Pad2)") (class "Default")
      (node (ref "C101") (pin "2") (pinfunction "2_2") (pintype "passive"))
      (node (ref "C104") (pin "2") (pinfunction "2_2") (pintype "passive"))
      (node (ref "K5") (pin "2") (pinfunction "2_2") (pintype "passive"))
      (node (ref "L40") (pin "1") (pinfunction "1_1") (pintype "passive"))
    )
    (net (code "125") (name "Net-(C120-Pad1)") (class "Default")
      (node (ref "C120") (pin "1") (pinfunction "1_1") (pintype "passive"))
      (node (ref "K3") (pin "5") (pinfunction "5_5") (pintype "passive"))
    )
    (net (code "126") (name "Net-(D12-(C))") (class "Default")
      (node (ref "C60") (pin "2") (pinfunction "2_2") (pintype "passive"))
      (node (ref "C63") (pin "2") (pinfunction "2_2") (pintype "passive"))
      (node (ref "D12") (pin "1") (pinfunction "(C)_1") (pintype "passive"))
      (node (ref "L24") (pin "2") (pinfunction "2_2") (pintype "passive"))
      (node (ref "L27") (pin "1") (pinfunction "1_1") (pintype "passive"))
    )
    (net (code "127") (name "Net-(D14-(C))") (class "Default")
      (node (ref "C74") (pin "2") (pinfunction "2_2") (pintype "passive"))
      (node (ref "C77") (pin "2") (pinfunction "2_2") (pintype "passive"))
      (node (ref "D14") (pin "1") (pinfunction "(C)_1") (pintype "passive"))
      (node (ref "L29") (pin "2") (pinfunction "2_2") (pintype "passive"))
      (node (ref "L32") (pin "1") (pinfunction "1_1") (pintype "passive"))
    )
    (net (code "128") (name "Net-(FAN_OUT--)") (class "Default")
      (node (ref "FAN_OUT") (pin "2") (pinfunction "-_2") (pintype "passive"))
      (node (ref "U4") (pin "15") (pinfunction "2C_15") (pintype "passive"))
    )
    (net (code "129") (name "Net-(K1-Pad2)") (class "Default")
      (node (ref "K1") (pin "2") (pinfunction "2_2") (pintype "passive"))
      (node (ref "K1") (pin "7") (pinfunction "7_7") (pintype "passive"))
    )
    (net (code "130") (name "Net-(K1-Pad4)") (class "Default")
      (node (ref "K1") (pin "4") (pinfunction "4_4") (pintype "passive"))
      (node (ref "R27") (pin "1") (pinfunction "1_1") (pintype "passive"))
    )
    (net (code "131") (name "Net-(K3-Pad2)") (class "Default")
      (node (ref "K3") (pin "2") (pinfunction "2_2") (pintype "passive"))
      (node (ref "K3") (pin "7") (pinfunction "7_7") (pintype "passive"))
    )
    (net (code "132") (name "Net-(K4-Pad4)") (class "Default")
      (node (ref "K4") (pin "4") (pinfunction "4_4") (pintype "passive"))
      (node (ref "K4") (pin "5") (pinfunction "5_5") (pintype "passive"))
    )
    (net (code "133") (name "Net-(K5-Pad4)") (class "Default")
      (node (ref "K5") (pin "4") (pinfunction "4_4") (pintype "passive"))
      (node (ref "K5") (pin "5") (pinfunction "5_5") (pintype "passive"))
    )
    (net (code "134") (name "Net-(L44-B)") (class "Default")
      (node (ref "C124") (pin "2") (pinfunction "2_2") (pintype "passive"))
      (node (ref "L44") (pin "2") (pinfunction "B_2") (pintype "passive"))
      (node (ref "L45") (pin "1") (pinfunction "A_1") (pintype "passive"))
    )
    (net (code "135") (name "Net-(L46-Pad1)") (class "Default")
      (node (ref "L46") (pin "1") (pinfunction "1_1") (pintype "passive"))
      (node (ref "R39") (pin "2") (pinfunction "2_2") (pintype "passive"))
    )
    (net (code "136") (name "Net-(Q4-D)") (class "Default")
      (node (ref "C120") (pin "2") (pinfunction "2_2") (pintype "passive"))
      (node (ref "L46") (pin "2") (pinfunction "2_2") (pintype "passive"))
      (node (ref "Q4") (pin "3") (pinfunction "D_3") (pintype "passive"))
    )
    (net (code "137") (name "Net-(U1-QH')") (class "Default")
      (node (ref "U1") (pin "9") (pinfunction "QH'_9") (pintype "output"))
      (node (ref "U7") (pin "14") (pinfunction "SER_14") (pintype "input"))
    )
    (net (code "138") (name "Net-(U1-QH)") (class "Default")
      (node (ref "U1") (pin "7") (pinfunction "QH_7") (pintype "tri_state"))
      (node (ref "U4") (pin "1") (pinfunction "1B_1") (pintype "passive"))
    )
    (net (code "139") (name "Net-(U1-SER)") (class "Default")
      (node (ref "U1") (pin "14") (pinfunction "SER_14") (pintype "input"))
      (node (ref "U3") (pin "9") (pinfunction "QH'_9") (pintype "output"))
    )
    (net (code "140") (name "Net-(U3-QA)") (class "Default")
      (node (ref "U3") (pin "15") (pinfunction "QA_15") (pintype "tri_state"))
      (node (ref "U4") (pin "7") (pinfunction "7B_7") (pintype "passive"))
    )
    (net (code "141") (name "Net-(U3-QB)") (class "Default")
      (node (ref "U3") (pin "1") (pinfunction "QB_1") (pintype "tri_state"))
      (node (ref "U4") (pin "6") (pinfunction "6B_6") (pintype "passive"))
    )
    (net (code "142") (name "Net-(U3-QC)") (class "Default")
      (node (ref "U3") (pin "2") (pinfunction "QC_2") (pintype "tri_state"))
      (node (ref "U4") (pin "5") (pinfunction "5B_5") (pintype "passive"))
    )
    (net (code "143") (name "Net-(U3-QD)") (class "Default")
      (node (ref "U3") (pin "3") (pinfunction "QD_3") (pintype "tri_state"))
      (node (ref "U4") (pin "4") (pinfunction "4B_4") (pintype "passive"))
    )
    (net (code "144") (name "Net-(U3-QE)") (class "Default")
      (node (ref "U3") (pin "4") (pinfunction "QE_4") (pintype "tri_state"))
      (node (ref "U4") (pin "3") (pinfunction "3B_3") (pintype "passive"))
    )
    (net (code "145") (name "Net-(U3-QF)") (class "Default")
      (node (ref "U3") (pin "5") (pinfunction "QF_5") (pintype "tri_state"))
      (node (ref "U4") (pin "2") (pinfunction "2B_2") (pintype "passive"))
    )
    (net (code "146") (name "Net-(U6-OUT)") (class "Default")
      (node (ref "C121") (pin "2") (pinfunction "2_2") (pintype "passive"))
      (node (ref "C122") (pin "2") (pinfunction "2_2") (pintype "passive"))
      (node (ref "C127") (pin "2") (pinfunction "2_2") (pintype "passive"))
      (node (ref "C133") (pin "2") (pinfunction "2_2") (pintype "passive"))
      (node (ref "R39") (pin "1") (pinfunction "1_1") (pintype "passive"))
      (node (ref "U6") (pin "2") (pinfunction "OUT_2") (pintype "passive"))
      (node (ref "U6") (pin "4") (pinfunction "Vout_4") (pintype "passive"))
    )
    (net (code "147") (name "RF_TX_IN") (class "Default")
      (node (ref "J9") (pin "2") (pinfunction "P2_2") (pintype "passive"))
      (node (ref "T5") (pin "11") (pinfunction "11_11") (pintype "passive"))
      (node (ref "T5") (pin "4") (pinfunction "P2_4") (pintype "passive"))
    )
    (net (code "148") (name "RX_ATT_LPF") (class "Default")
      (node (ref "K1") (pin "6") (pinfunction "6_6") (pintype "passive"))
      (node (ref "K5") (pin "3") (pinfunction "3_3") (pintype "passive"))
    )
    (net (code "149") (name "RX_BPF_OUT") (class "Default")
      (node (ref "J2") (pin "2") (pinfunction "P2_2") (pintype "passive"))
      (node (ref "K4") (pin "6") (pinfunction "6_6") (pintype "passive"))
    )
    (net (code "150") (name "RX_IN_LNA") (class "Default")
      (node (ref "D24") (pin "3") (pinfunction "C(D1),A(D2)_3") (pintype "passive"))
      (node (ref "K2") (pin "2") (pinfunction "O_2") (pintype "passive"))
      (node (ref "K3") (pin "3") (pinfunction "3_3") (pintype "passive"))
    )
    (net (code "151") (name "RX_LNA_ATT") (class "Default")
      (node (ref "K1") (pin "3") (pinfunction "3_3") (pintype "passive"))
      (node (ref "K3") (pin "6") (pinfunction "6_6") (pintype "passive"))
    )
    (net (code "152") (name "RX_LPF_BPF") (class "Default")
      (node (ref "K4") (pin "3") (pinfunction "3_3") (pintype "passive"))
      (node (ref "K5") (pin "6") (pinfunction "6_6") (pintype "passive"))
    )
    (net (code "153") (name "SWR_DET_BACKW") (class "Default")
      (node (ref "J4") (pin "8") (pinfunction "SWR_F_8") (pintype "passive"))
      (node (ref "R50") (pin "2") (pinfunction "2_2") (pintype "passive"))
      (node (ref "R54") (pin "2") (pinfunction "2_2") (pintype "passive"))
    )
    (net (code "154") (name "SWR_DET_FORW") (class "Default")
      (node (ref "J4") (pin "7") (pinfunction "SWR_B_7") (pintype "passive"))
      (node (ref "R36") (pin "1") (pinfunction "1_1") (pintype "passive"))
      (node (ref "R49") (pin "2") (pinfunction "2_2") (pintype "passive"))
    )
    (net (code "155") (name "SWR_OUT") (class "Default")
      (node (ref "K2") (pin "4") (pinfunction "S_4") (pintype "passive"))
      (node (ref "TSWR") (pin "2") (pinfunction "2_2") (pintype "passive"))
      (node (ref "TSWR") (pin "5") (pinfunction "5_5") (pintype "passive"))
    )
    (net (code "156") (name "TXAMP_ENABLE") (class "Default")
      (node (ref "Q2") (pin "1") (pinfunction "G_1") (pintype "passive"))
      (node (ref "R41") (pin "1") (pinfunction "1_1") (pintype "passive"))
      (node (ref "U4") (pin "16") (pinfunction "1C_16") (pintype "passive"))
    )
    (net (code "157") (name "TXRX_RELAY") (class "Default")
      (node (ref "D3") (pin "2") (pinfunction "A_2") (pintype "passive"))
      (node (ref "K2") (pin "8") (pinfunction "-_8") (pintype "passive"))
      (node (ref "U8") (pin "16") (pinfunction "1C_16") (pintype "passive"))
    )
    (net (code "158") (name "TX_LPF_OUT") (class "Default")
      (node (ref "C125") (pin "2") (pinfunction "2_2") (pintype "passive"))
      (node (ref "L45") (pin "2") (pinfunction "B_2") (pintype "passive"))
      (node (ref "TSWR") (pin "1") (pinfunction "1_1") (pintype "passive"))
    )
    (net (code "159") (name "unconnected-(K2-O-Pad7)") (class "Default")
      (node (ref "K2") (pin "7") (pinfunction "O_7") (pintype "passive"))
    )
    (net (code "160") (name "unconnected-(K2-P-Pad6)") (class "Default")
      (node (ref "K2") (pin "6") (pinfunction "P_6") (pintype "passive"))
    )
    (net (code "161") (name "unconnected-(K2-S-Pad5)") (class "Default")
      (node (ref "K2") (pin "5") (pinfunction "S_5") (pintype "passive"))
    )
    (net (code "162") (name "unconnected-(T1-S2-Pad2)") (class "Default")
      (node (ref "T1") (pin "2") (pinfunction "S2_2") (pintype "passive"))
    )
    (net (code "163") (name "unconnected-(T2-S2-Pad2)") (class "Default")
      (node (ref "T2") (pin "2") (pinfunction "S2_2") (pintype "passive"))
    )
    (net (code "164") (name "unconnected-(U2-1C-Pad16)") (class "Default")
      (node (ref "U2") (pin "16") (pinfunction "1C_16") (pintype "passive"))
    )
    (net (code "165") (name "unconnected-(U3-QG-Pad6)") (class "Default")
      (node (ref "U3") (pin "6") (pinfunction "QG_6") (pintype "tri_state"))
    )
    (net (code "166") (name "unconnected-(U3-QH-Pad7)") (class "Default")
      (node (ref "U3") (pin "7") (pinfunction "QH_7") (pintype "tri_state"))
    )
    (net (code "167") (name "unconnected-(U7-QH'-Pad9)") (class "Default")
      (node (ref "U7") (pin "9") (pinfunction "QH'_9") (pintype "output"))
    )
    (net (code "168") (name "unconnected-(U7-QH-Pad7)") (class "Default")
      (node (ref "U7") (pin "7") (pinfunction "QH_7") (pintype "tri_state"))
    )
    (net (code "169") (name "unconnected-(U8-2C-Pad15)") (class "Default")
      (node (ref "U8") (pin "15") (pinfunction "2C_15") (pintype "passive"))
    )
    (net (code "170") (name "unconnected-(U8-3C-Pad14)") (class "Default")
      (node (ref "U8") (pin "14") (pinfunction "3C_14") (pintype "passive"))
    )
    (net (code "171") (name "unconnected-(U8-4C-Pad13)") (class "Default")
      (node (ref "U8") (pin "13") (pinfunction "4C_13") (pintype "passive"))
    )
    (net (code "172") (name "unconnected-(U8-5C-Pad12)") (class "Default")
      (node (ref "U8") (pin "12") (pinfunction "5C_12") (pintype "passive"))
    )
    (net (code "173") (name "unconnected-(U8-6C-Pad11)") (class "Default")
      (node (ref "U8") (pin "11") (pinfunction "6C_11") (pintype "passive"))
    )
  )
)
